# 04_-_CPU_-_DDR3_DDR3_MEM.net
KiCad netlist of a schematic drawn in Altium Designer
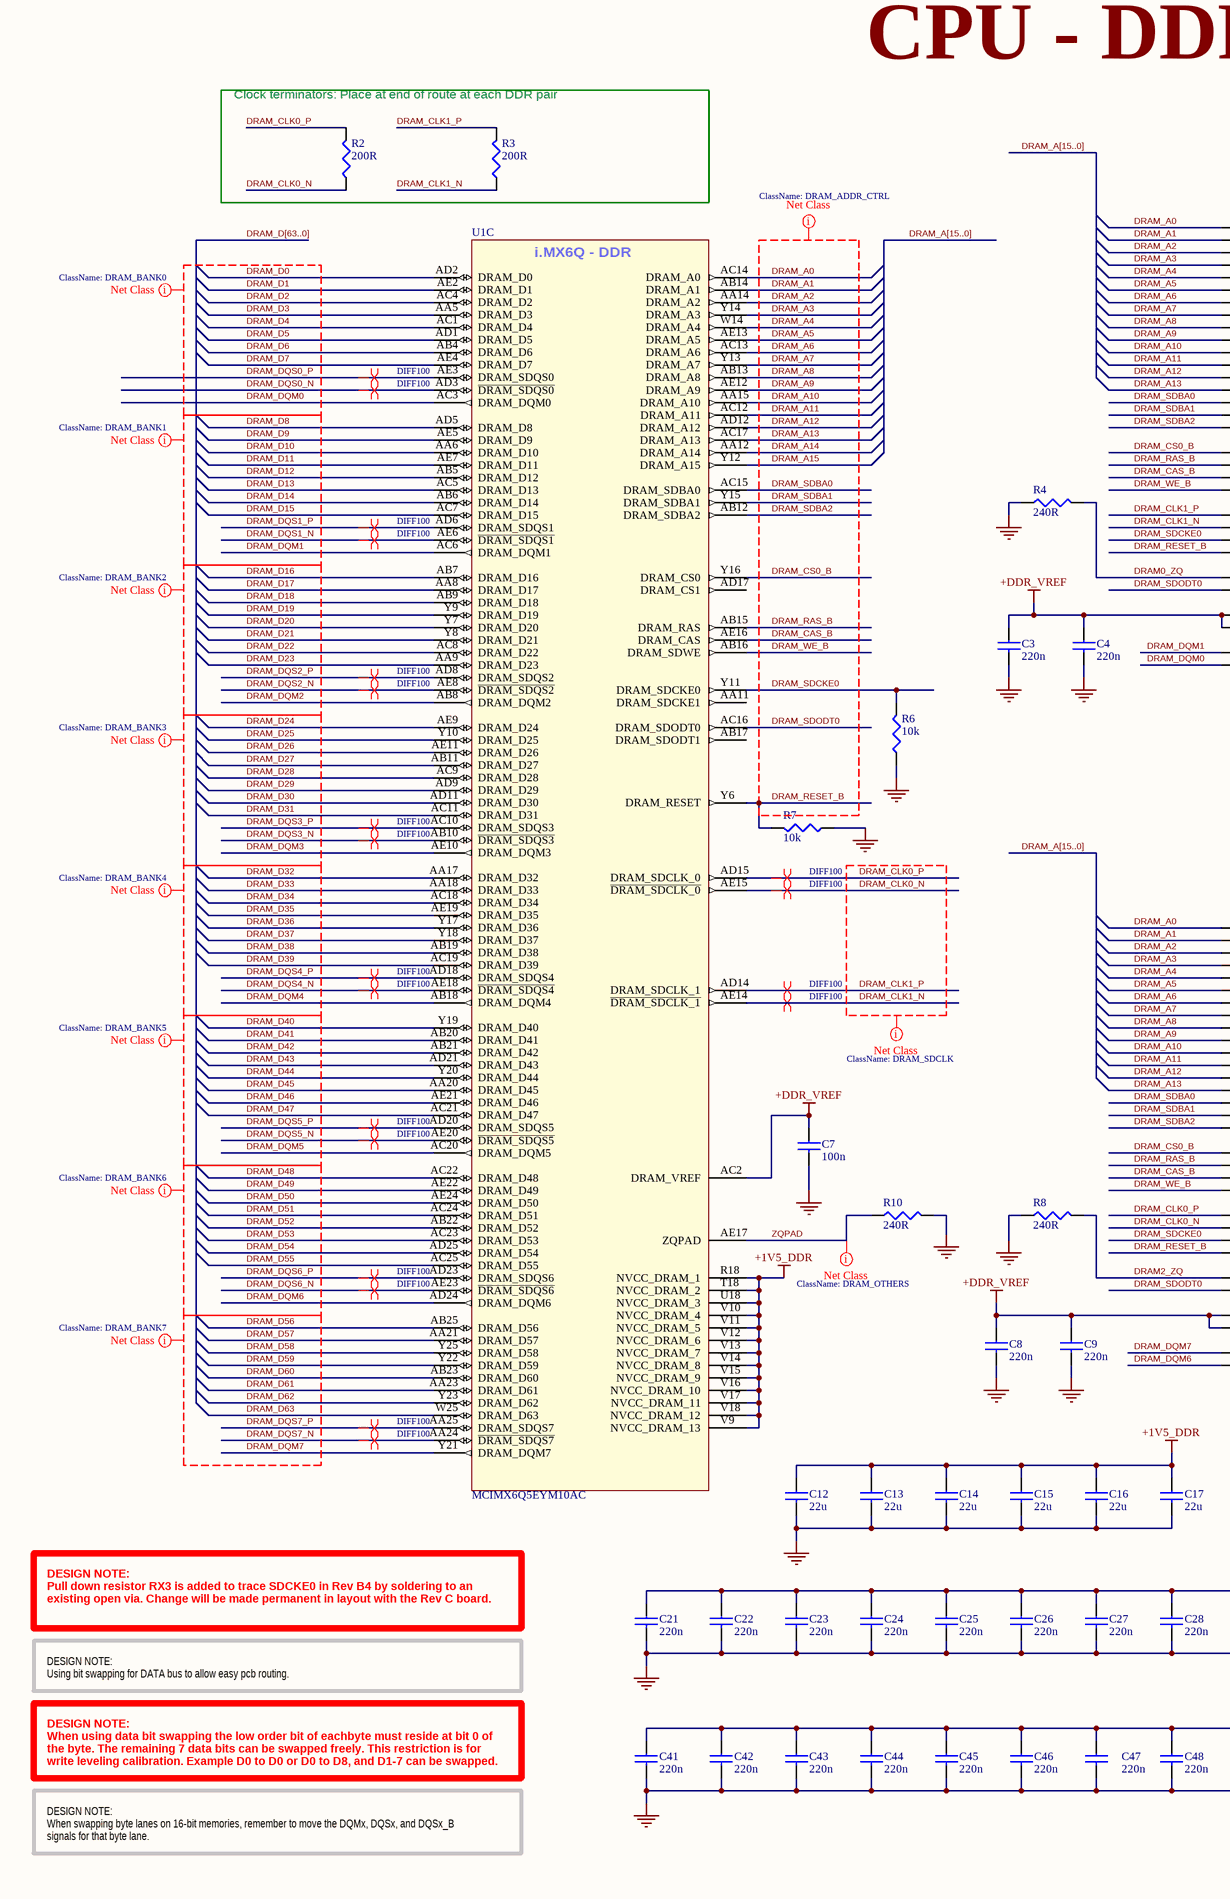
[diagram p0: [04] - CPU - DDR3, DDR3 MEM.SchDoc, left]
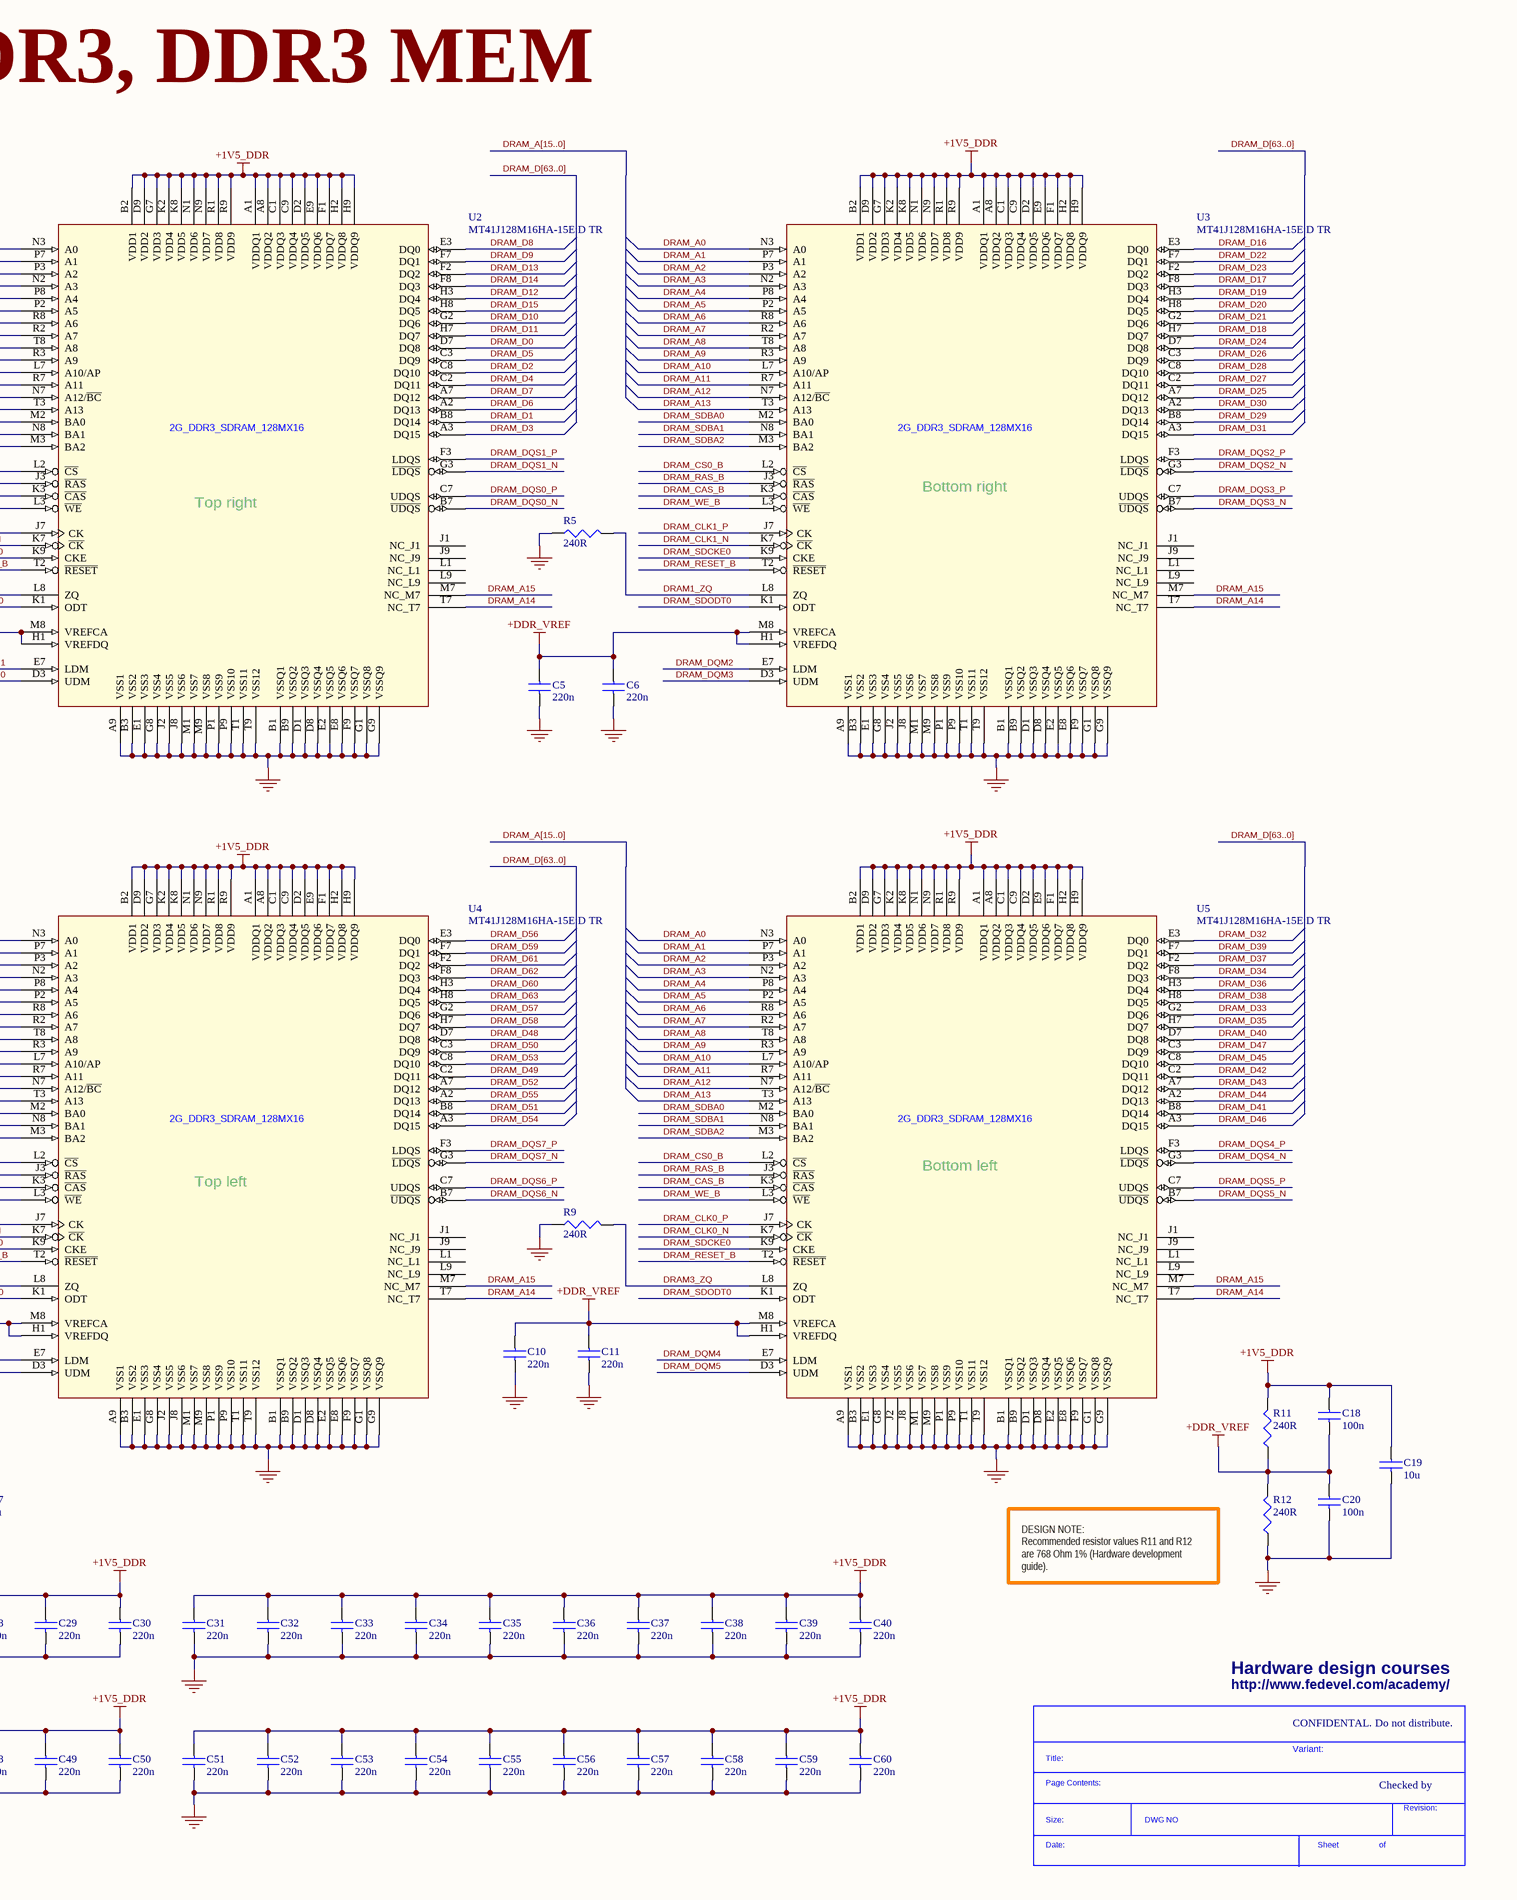
[diagram p1: [04] - CPU - DDR3, DDR3 MEM.SchDoc, right]

(export (version "E")
  (design (tool "Eeschema 10.0.6"))
  (components
    (comp (ref "C3")
      (value "220n")
      (footprint "C0402")
      (description "CAP CER .22UF 25V X5R 20% 0402")
      (fields
        (field (name "MANUFACTURER") "TDK Corporation")
        (field (name "MANUFACTURER PART NUMBER") "C1005X5R1E224M")
      )
      (libsource (lib "iMX6 Rex_V1I1") (part "C1005X5R1E224M"))
    )
    (comp (ref "C4")
      (value "220n")
      (footprint "C0402")
      (description "CAP CER .22UF 25V X5R 20% 0402")
      (fields
        (field (name "MANUFACTURER") "TDK Corporation")
        (field (name "MANUFACTURER PART NUMBER") "C1005X5R1E224M")
      )
      (libsource (lib "iMX6 Rex_V1I1") (part "C1005X5R1E224M"))
    )
    (comp (ref "C5")
      (value "220n")
      (footprint "C0402")
      (description "CAP CER .22UF 25V X5R 20% 0402")
      (fields
        (field (name "MANUFACTURER") "TDK Corporation")
        (field (name "MANUFACTURER PART NUMBER") "C1005X5R1E224M")
      )
      (libsource (lib "iMX6 Rex_V1I1") (part "C1005X5R1E224M"))
    )
    (comp (ref "C6")
      (value "220n")
      (footprint "C0402")
      (description "CAP CER .22UF 25V X5R 20% 0402")
      (fields
        (field (name "MANUFACTURER") "TDK Corporation")
        (field (name "MANUFACTURER PART NUMBER") "C1005X5R1E224M")
      )
      (libsource (lib "iMX6 Rex_V1I1") (part "C1005X5R1E224M"))
    )
    (comp (ref "C7")
      (value "100n")
      (footprint "C0402")
      (description "CAP CER .10UF 50V X5R 10% 0402")
      (fields
        (field (name "MANUFACTURER") "TDK Corporation")
        (field (name "MANUFACTURER PART NUMBER") "C1005X5R1H104K")
      )
      (libsource (lib "iMX6 Rex_V1I1") (part "C1005X5R1H104K"))
    )
    (comp (ref "C8")
      (value "220n")
      (footprint "C0402")
      (description "CAP CER .22UF 25V X5R 20% 0402")
      (fields
        (field (name "MANUFACTURER") "TDK Corporation")
        (field (name "MANUFACTURER PART NUMBER") "C1005X5R1E224M")
      )
      (libsource (lib "iMX6 Rex_V1I1") (part "C1005X5R1E224M"))
    )
    (comp (ref "C9")
      (value "220n")
      (footprint "C0402")
      (description "CAP CER .22UF 25V X5R 20% 0402")
      (fields
        (field (name "MANUFACTURER") "TDK Corporation")
        (field (name "MANUFACTURER PART NUMBER") "C1005X5R1E224M")
      )
      (libsource (lib "iMX6 Rex_V1I1") (part "C1005X5R1E224M"))
    )
    (comp (ref "C10")
      (value "220n")
      (footprint "C0402")
      (description "CAP CER .22UF 25V X5R 20% 0402")
      (fields
        (field (name "MANUFACTURER") "TDK Corporation")
        (field (name "MANUFACTURER PART NUMBER") "C1005X5R1E224M")
      )
      (libsource (lib "iMX6 Rex_V1I1") (part "C1005X5R1E224M"))
    )
    (comp (ref "C11")
      (value "220n")
      (footprint "C0402")
      (description "CAP CER .22UF 25V X5R 20% 0402")
      (fields
        (field (name "MANUFACTURER") "TDK Corporation")
        (field (name "MANUFACTURER PART NUMBER") "C1005X5R1E224M")
      )
      (libsource (lib "iMX6 Rex_V1I1") (part "C1005X5R1E224M"))
    )
    (comp (ref "C12")
      (value "22u")
      (footprint "C0603")
      (description "CAP CER 22UF 4V 20% X5R 0603")
      (fields
        (field (name "MANUFACTURER") "Murata Electronics North America")
        (field (name "MANUFACTURER PART NUMBER") "GRM188R60G226MEA0L")
        (field (name ".CHECKED PCB") "RF, used by MM")
        (field (name ".CHECKED SCH") "MM, checked by RF")
        (field (name ".CREATOR") "MM")
      )
      (libsource (lib "iMX6 Rex_V1I1") (part "GRM188R60G226MEA0L"))
    )
    (comp (ref "C13")
      (value "22u")
      (footprint "C0603")
      (description "CAP CER 22UF 4V 20% X5R 0603")
      (fields
        (field (name "MANUFACTURER") "Murata Electronics North America")
        (field (name "MANUFACTURER PART NUMBER") "GRM188R60G226MEA0L")
        (field (name ".CHECKED PCB") "RF, used by MM")
        (field (name ".CHECKED SCH") "MM, checked by RF")
        (field (name ".CREATOR") "MM")
      )
      (libsource (lib "iMX6 Rex_V1I1") (part "GRM188R60G226MEA0L"))
    )
    (comp (ref "C14")
      (value "22u")
      (footprint "C0603")
      (description "CAP CER 22UF 4V 20% X5R 0603")
      (fields
        (field (name "MANUFACTURER") "Murata Electronics North America")
        (field (name "MANUFACTURER PART NUMBER") "GRM188R60G226MEA0L")
        (field (name ".CHECKED PCB") "RF, used by MM")
        (field (name ".CHECKED SCH") "MM, checked by RF")
        (field (name ".CREATOR") "MM")
      )
      (libsource (lib "iMX6 Rex_V1I1") (part "GRM188R60G226MEA0L"))
    )
    (comp (ref "C15")
      (value "22u")
      (footprint "C0603")
      (description "CAP CER 22UF 4V 20% X5R 0603")
      (fields
        (field (name "MANUFACTURER") "Murata Electronics North America")
        (field (name "MANUFACTURER PART NUMBER") "GRM188R60G226MEA0L")
        (field (name ".CHECKED PCB") "RF, used by MM")
        (field (name ".CHECKED SCH") "MM, checked by RF")
        (field (name ".CREATOR") "MM")
      )
      (libsource (lib "iMX6 Rex_V1I1") (part "GRM188R60G226MEA0L"))
    )
    (comp (ref "C16")
      (value "22u")
      (footprint "C0603")
      (description "CAP CER 22UF 4V 20% X5R 0603")
      (fields
        (field (name "MANUFACTURER") "Murata Electronics North America")
        (field (name "MANUFACTURER PART NUMBER") "GRM188R60G226MEA0L")
        (field (name ".CHECKED PCB") "RF, used by MM")
        (field (name ".CHECKED SCH") "MM, checked by RF")
        (field (name ".CREATOR") "MM")
      )
      (libsource (lib "iMX6 Rex_V1I1") (part "GRM188R60G226MEA0L"))
    )
    (comp (ref "C17")
      (value "22u")
      (footprint "C0603")
      (description "CAP CER 22UF 4V 20% X5R 0603")
      (fields
        (field (name "MANUFACTURER") "Murata Electronics North America")
        (field (name "MANUFACTURER PART NUMBER") "GRM188R60G226MEA0L")
        (field (name ".CHECKED PCB") "RF, used by MM")
        (field (name ".CHECKED SCH") "MM, checked by RF")
        (field (name ".CREATOR") "MM")
      )
      (libsource (lib "iMX6 Rex_V1I1") (part "GRM188R60G226MEA0L"))
    )
    (comp (ref "C18")
      (value "100n")
      (footprint "C0402")
      (description "CAP CER .10UF 50V X5R 10% 0402")
      (fields
        (field (name "MANUFACTURER") "TDK Corporation")
        (field (name "MANUFACTURER PART NUMBER") "C1005X5R1H104K")
      )
      (libsource (lib "iMX6 Rex_V1I1") (part "C1005X5R1H104K"))
    )
    (comp (ref "C19")
      (value "10u")
      (footprint "C0603")
      (description "CAP CER 10UF 6.3V X5R 20% 0603")
      (fields
        (field (name "MANUFACTURER") "TDK Corporation")
        (field (name "MANUFACTURER PART NUMBER") "C1608X5R0J106M")
      )
      (libsource (lib "iMX6 Rex_V1I1") (part "C1608X5R0J106M"))
    )
    (comp (ref "C20")
      (value "100n")
      (footprint "C0402")
      (description "CAP CER .10UF 50V X5R 10% 0402")
      (fields
        (field (name "MANUFACTURER") "TDK Corporation")
        (field (name "MANUFACTURER PART NUMBER") "C1005X5R1H104K")
      )
      (libsource (lib "iMX6 Rex_V1I1") (part "C1005X5R1H104K"))
    )
    (comp (ref "C21")
      (value "220n")
      (footprint "C0402")
      (description "CAP CER .22UF 25V X5R 20% 0402")
      (fields
        (field (name "MANUFACTURER") "TDK Corporation")
        (field (name "MANUFACTURER PART NUMBER") "C1005X5R1E224M")
      )
      (libsource (lib "iMX6 Rex_V1I1") (part "C1005X5R1E224M"))
    )
    (comp (ref "C22")
      (value "220n")
      (footprint "C0402")
      (description "CAP CER .22UF 25V X5R 20% 0402")
      (fields
        (field (name "MANUFACTURER") "TDK Corporation")
        (field (name "MANUFACTURER PART NUMBER") "C1005X5R1E224M")
      )
      (libsource (lib "iMX6 Rex_V1I1") (part "C1005X5R1E224M"))
    )
    (comp (ref "C23")
      (value "220n")
      (footprint "C0402")
      (description "CAP CER .22UF 25V X5R 20% 0402")
      (fields
        (field (name "MANUFACTURER") "TDK Corporation")
        (field (name "MANUFACTURER PART NUMBER") "C1005X5R1E224M")
      )
      (libsource (lib "iMX6 Rex_V1I1") (part "C1005X5R1E224M"))
    )
    (comp (ref "C24")
      (value "220n")
      (footprint "C0402")
      (description "CAP CER .22UF 25V X5R 20% 0402")
      (fields
        (field (name "MANUFACTURER") "TDK Corporation")
        (field (name "MANUFACTURER PART NUMBER") "C1005X5R1E224M")
      )
      (libsource (lib "iMX6 Rex_V1I1") (part "C1005X5R1E224M"))
    )
    (comp (ref "C25")
      (value "220n")
      (footprint "C0402")
      (description "CAP CER .22UF 25V X5R 20% 0402")
      (fields
        (field (name "MANUFACTURER") "TDK Corporation")
        (field (name "MANUFACTURER PART NUMBER") "C1005X5R1E224M")
      )
      (libsource (lib "iMX6 Rex_V1I1") (part "C1005X5R1E224M"))
    )
    (comp (ref "C26")
      (value "220n")
      (footprint "C0402")
      (description "CAP CER .22UF 25V X5R 20% 0402")
      (fields
        (field (name "MANUFACTURER") "TDK Corporation")
        (field (name "MANUFACTURER PART NUMBER") "C1005X5R1E224M")
      )
      (libsource (lib "iMX6 Rex_V1I1") (part "C1005X5R1E224M"))
    )
    (comp (ref "C27")
      (value "220n")
      (footprint "C0402")
      (description "CAP CER .22UF 25V X5R 20% 0402")
      (fields
        (field (name "MANUFACTURER") "TDK Corporation")
        (field (name "MANUFACTURER PART NUMBER") "C1005X5R1E224M")
      )
      (libsource (lib "iMX6 Rex_V1I1") (part "C1005X5R1E224M"))
    )
    (comp (ref "C28")
      (value "220n")
      (footprint "C0402")
      (description "CAP CER .22UF 25V X5R 20% 0402")
      (fields
        (field (name "MANUFACTURER") "TDK Corporation")
        (field (name "MANUFACTURER PART NUMBER") "C1005X5R1E224M")
      )
      (libsource (lib "iMX6 Rex_V1I1") (part "C1005X5R1E224M"))
    )
    (comp (ref "C29")
      (value "220n")
      (footprint "C0402")
      (description "CAP CER .22UF 25V X5R 20% 0402")
      (fields
        (field (name "MANUFACTURER") "TDK Corporation")
        (field (name "MANUFACTURER PART NUMBER") "C1005X5R1E224M")
      )
      (libsource (lib "iMX6 Rex_V1I1") (part "C1005X5R1E224M"))
    )
    (comp (ref "C30")
      (value "220n")
      (footprint "C0402")
      (description "CAP CER .22UF 25V X5R 20% 0402")
      (fields
        (field (name "MANUFACTURER") "TDK Corporation")
        (field (name "MANUFACTURER PART NUMBER") "C1005X5R1E224M")
      )
      (libsource (lib "iMX6 Rex_V1I1") (part "C1005X5R1E224M"))
    )
    (comp (ref "C31")
      (value "220n")
      (footprint "C0402")
      (description "CAP CER .22UF 25V X5R 20% 0402")
      (fields
        (field (name "MANUFACTURER") "TDK Corporation")
        (field (name "MANUFACTURER PART NUMBER") "C1005X5R1E224M")
      )
      (libsource (lib "iMX6 Rex_V1I1") (part "C1005X5R1E224M"))
    )
    (comp (ref "C32")
      (value "220n")
      (footprint "C0402")
      (description "CAP CER .22UF 25V X5R 20% 0402")
      (fields
        (field (name "MANUFACTURER") "TDK Corporation")
        (field (name "MANUFACTURER PART NUMBER") "C1005X5R1E224M")
      )
      (libsource (lib "iMX6 Rex_V1I1") (part "C1005X5R1E224M"))
    )
    (comp (ref "C33")
      (value "220n")
      (footprint "C0402")
      (description "CAP CER .22UF 25V X5R 20% 0402")
      (fields
        (field (name "MANUFACTURER") "TDK Corporation")
        (field (name "MANUFACTURER PART NUMBER") "C1005X5R1E224M")
      )
      (libsource (lib "iMX6 Rex_V1I1") (part "C1005X5R1E224M"))
    )
    (comp (ref "C34")
      (value "220n")
      (footprint "C0402")
      (description "CAP CER .22UF 25V X5R 20% 0402")
      (fields
        (field (name "MANUFACTURER") "TDK Corporation")
        (field (name "MANUFACTURER PART NUMBER") "C1005X5R1E224M")
      )
      (libsource (lib "iMX6 Rex_V1I1") (part "C1005X5R1E224M"))
    )
    (comp (ref "C35")
      (value "220n")
      (footprint "C0402")
      (description "CAP CER .22UF 25V X5R 20% 0402")
      (fields
        (field (name "MANUFACTURER") "TDK Corporation")
        (field (name "MANUFACTURER PART NUMBER") "C1005X5R1E224M")
      )
      (libsource (lib "iMX6 Rex_V1I1") (part "C1005X5R1E224M"))
    )
    (comp (ref "C36")
      (value "220n")
      (footprint "C0402")
      (description "CAP CER .22UF 25V X5R 20% 0402")
      (fields
        (field (name "MANUFACTURER") "TDK Corporation")
        (field (name "MANUFACTURER PART NUMBER") "C1005X5R1E224M")
      )
      (libsource (lib "iMX6 Rex_V1I1") (part "C1005X5R1E224M"))
    )
    (comp (ref "C37")
      (value "220n")
      (footprint "C0402")
      (description "CAP CER .22UF 25V X5R 20% 0402")
      (fields
        (field (name "MANUFACTURER") "TDK Corporation")
        (field (name "MANUFACTURER PART NUMBER") "C1005X5R1E224M")
      )
      (libsource (lib "iMX6 Rex_V1I1") (part "C1005X5R1E224M"))
    )
    (comp (ref "C38")
      (value "220n")
      (footprint "C0402")
      (description "CAP CER .22UF 25V X5R 20% 0402")
      (fields
        (field (name "MANUFACTURER") "TDK Corporation")
        (field (name "MANUFACTURER PART NUMBER") "C1005X5R1E224M")
      )
      (libsource (lib "iMX6 Rex_V1I1") (part "C1005X5R1E224M"))
    )
    (comp (ref "C39")
      (value "220n")
      (footprint "C0402")
      (description "CAP CER .22UF 25V X5R 20% 0402")
      (fields
        (field (name "MANUFACTURER") "TDK Corporation")
        (field (name "MANUFACTURER PART NUMBER") "C1005X5R1E224M")
      )
      (libsource (lib "iMX6 Rex_V1I1") (part "C1005X5R1E224M"))
    )
    (comp (ref "C40")
      (value "220n")
      (footprint "C0402")
      (description "CAP CER .22UF 25V X5R 20% 0402")
      (fields
        (field (name "MANUFACTURER") "TDK Corporation")
        (field (name "MANUFACTURER PART NUMBER") "C1005X5R1E224M")
      )
      (libsource (lib "iMX6 Rex_V1I1") (part "C1005X5R1E224M"))
    )
    (comp (ref "C41")
      (value "220n")
      (footprint "C0402")
      (description "CAP CER .22UF 25V X5R 20% 0402")
      (fields
        (field (name "MANUFACTURER") "TDK Corporation")
        (field (name "MANUFACTURER PART NUMBER") "C1005X5R1E224M")
      )
      (libsource (lib "iMX6 Rex_V1I1") (part "C1005X5R1E224M"))
    )
    (comp (ref "C42")
      (value "220n")
      (footprint "C0402")
      (description "CAP CER .22UF 25V X5R 20% 0402")
      (fields
        (field (name "MANUFACTURER") "TDK Corporation")
        (field (name "MANUFACTURER PART NUMBER") "C1005X5R1E224M")
      )
      (libsource (lib "iMX6 Rex_V1I1") (part "C1005X5R1E224M"))
    )
    (comp (ref "C43")
      (value "220n")
      (footprint "C0402")
      (description "CAP CER .22UF 25V X5R 20% 0402")
      (fields
        (field (name "MANUFACTURER") "TDK Corporation")
        (field (name "MANUFACTURER PART NUMBER") "C1005X5R1E224M")
      )
      (libsource (lib "iMX6 Rex_V1I1") (part "C1005X5R1E224M"))
    )
    (comp (ref "C44")
      (value "220n")
      (footprint "C0402")
      (description "CAP CER .22UF 25V X5R 20% 0402")
      (fields
        (field (name "MANUFACTURER") "TDK Corporation")
        (field (name "MANUFACTURER PART NUMBER") "C1005X5R1E224M")
      )
      (libsource (lib "iMX6 Rex_V1I1") (part "C1005X5R1E224M"))
    )
    (comp (ref "C45")
      (value "220n")
      (footprint "C0402")
      (description "CAP CER .22UF 25V X5R 20% 0402")
      (fields
        (field (name "MANUFACTURER") "TDK Corporation")
        (field (name "MANUFACTURER PART NUMBER") "C1005X5R1E224M")
      )
      (libsource (lib "iMX6 Rex_V1I1") (part "C1005X5R1E224M"))
    )
    (comp (ref "C46")
      (value "220n")
      (footprint "C0402")
      (description "CAP CER .22UF 25V X5R 20% 0402")
      (fields
        (field (name "MANUFACTURER") "TDK Corporation")
        (field (name "MANUFACTURER PART NUMBER") "C1005X5R1E224M")
      )
      (libsource (lib "iMX6 Rex_V1I1") (part "C1005X5R1E224M"))
    )
    (comp (ref "C47")
      (value "220n")
      (footprint "C0402")
      (description "CAP CER .22UF 25V X5R 20% 0402")
      (fields
        (field (name "MANUFACTURER") "TDK Corporation")
        (field (name "MANUFACTURER PART NUMBER") "C1005X5R1E224M")
      )
      (libsource (lib "iMX6 Rex_V1I1") (part "C1005X5R1E224M"))
    )
    (comp (ref "C48")
      (value "220n")
      (footprint "C0402")
      (description "CAP CER .22UF 25V X5R 20% 0402")
      (fields
        (field (name "MANUFACTURER") "TDK Corporation")
        (field (name "MANUFACTURER PART NUMBER") "C1005X5R1E224M")
      )
      (libsource (lib "iMX6 Rex_V1I1") (part "C1005X5R1E224M"))
    )
    (comp (ref "C49")
      (value "220n")
      (footprint "C0402")
      (description "CAP CER .22UF 25V X5R 20% 0402")
      (fields
        (field (name "MANUFACTURER") "TDK Corporation")
        (field (name "MANUFACTURER PART NUMBER") "C1005X5R1E224M")
      )
      (libsource (lib "iMX6 Rex_V1I1") (part "C1005X5R1E224M"))
    )
    (comp (ref "C50")
      (value "220n")
      (footprint "C0402")
      (description "CAP CER .22UF 25V X5R 20% 0402")
      (fields
        (field (name "MANUFACTURER") "TDK Corporation")
        (field (name "MANUFACTURER PART NUMBER") "C1005X5R1E224M")
      )
      (libsource (lib "iMX6 Rex_V1I1") (part "C1005X5R1E224M"))
    )
    (comp (ref "C51")
      (value "220n")
      (footprint "C0402")
      (description "CAP CER .22UF 25V X5R 20% 0402")
      (fields
        (field (name "MANUFACTURER") "TDK Corporation")
        (field (name "MANUFACTURER PART NUMBER") "C1005X5R1E224M")
      )
      (libsource (lib "iMX6 Rex_V1I1") (part "C1005X5R1E224M"))
    )
    (comp (ref "C52")
      (value "220n")
      (footprint "C0402")
      (description "CAP CER .22UF 25V X5R 20% 0402")
      (fields
        (field (name "MANUFACTURER") "TDK Corporation")
        (field (name "MANUFACTURER PART NUMBER") "C1005X5R1E224M")
      )
      (libsource (lib "iMX6 Rex_V1I1") (part "C1005X5R1E224M"))
    )
    (comp (ref "C53")
      (value "220n")
      (footprint "C0402")
      (description "CAP CER .22UF 25V X5R 20% 0402")
      (fields
        (field (name "MANUFACTURER") "TDK Corporation")
        (field (name "MANUFACTURER PART NUMBER") "C1005X5R1E224M")
      )
      (libsource (lib "iMX6 Rex_V1I1") (part "C1005X5R1E224M"))
    )
    (comp (ref "C54")
      (value "220n")
      (footprint "C0402")
      (description "CAP CER .22UF 25V X5R 20% 0402")
      (fields
        (field (name "MANUFACTURER") "TDK Corporation")
        (field (name "MANUFACTURER PART NUMBER") "C1005X5R1E224M")
      )
      (libsource (lib "iMX6 Rex_V1I1") (part "C1005X5R1E224M"))
    )
    (comp (ref "C55")
      (value "220n")
      (footprint "C0402")
      (description "CAP CER .22UF 25V X5R 20% 0402")
      (fields
        (field (name "MANUFACTURER") "TDK Corporation")
        (field (name "MANUFACTURER PART NUMBER") "C1005X5R1E224M")
      )
      (libsource (lib "iMX6 Rex_V1I1") (part "C1005X5R1E224M"))
    )
    (comp (ref "C56")
      (value "220n")
      (footprint "C0402")
      (description "CAP CER .22UF 25V X5R 20% 0402")
      (fields
        (field (name "MANUFACTURER") "TDK Corporation")
        (field (name "MANUFACTURER PART NUMBER") "C1005X5R1E224M")
      )
      (libsource (lib "iMX6 Rex_V1I1") (part "C1005X5R1E224M"))
    )
    (comp (ref "C57")
      (value "220n")
      (footprint "C0402")
      (description "CAP CER .22UF 25V X5R 20% 0402")
      (fields
        (field (name "MANUFACTURER") "TDK Corporation")
        (field (name "MANUFACTURER PART NUMBER") "C1005X5R1E224M")
      )
      (libsource (lib "iMX6 Rex_V1I1") (part "C1005X5R1E224M"))
    )
    (comp (ref "C58")
      (value "220n")
      (footprint "C0402")
      (description "CAP CER .22UF 25V X5R 20% 0402")
      (fields
        (field (name "MANUFACTURER") "TDK Corporation")
        (field (name "MANUFACTURER PART NUMBER") "C1005X5R1E224M")
      )
      (libsource (lib "iMX6 Rex_V1I1") (part "C1005X5R1E224M"))
    )
    (comp (ref "C59")
      (value "220n")
      (footprint "C0402")
      (description "CAP CER .22UF 25V X5R 20% 0402")
      (fields
        (field (name "MANUFACTURER") "TDK Corporation")
        (field (name "MANUFACTURER PART NUMBER") "C1005X5R1E224M")
      )
      (libsource (lib "iMX6 Rex_V1I1") (part "C1005X5R1E224M"))
    )
    (comp (ref "C60")
      (value "220n")
      (footprint "C0402")
      (description "CAP CER .22UF 25V X5R 20% 0402")
      (fields
        (field (name "MANUFACTURER") "TDK Corporation")
        (field (name "MANUFACTURER PART NUMBER") "C1005X5R1E224M")
      )
      (libsource (lib "iMX6 Rex_V1I1") (part "C1005X5R1E224M"))
    )
    (comp (ref "R2")
      (value "200R")
      (footprint "R0402")
      (description "RES 200 OHM 1/16W 1% 0402 SMD")
      (fields
        (field (name "MANUFACTURER") "Vishay Dale")
        (field (name "MANUFACTURER PART NUMBER") "CRCW0402200RFKED")
        (field (name ".CHECKED PCB") "RF, used by MM")
        (field (name ".CHECKED SCH") "MM, checked by RF")
        (field (name ".CREATOR") "MM")
      )
      (libsource (lib "iMX6 Rex_V1I1") (part "CRCW0402200RFKED"))
    )
    (comp (ref "R3")
      (value "200R")
      (footprint "R0402")
      (description "RES 200 OHM 1/16W 1% 0402 SMD")
      (fields
        (field (name "MANUFACTURER") "Vishay Dale")
        (field (name "MANUFACTURER PART NUMBER") "CRCW0402200RFKED")
        (field (name ".CHECKED PCB") "RF, used by MM")
        (field (name ".CHECKED SCH") "MM, checked by RF")
        (field (name ".CREATOR") "MM")
      )
      (libsource (lib "iMX6 Rex_V1I1") (part "CRCW0402200RFKED"))
    )
    (comp (ref "R4")
      (value "240R")
      (footprint "R0402")
      (description "RES TF 240 OHM 1% 0.0625W 0402")
      (fields
        (field (name "MANUFACTURER") "Stackpole Electronics Inc")
        (field (name "MANUFACTURER PART NUMBER") "RMCF0402FT240R")
      )
      (libsource (lib "iMX6 Rex_V1I1") (part "RMCF0402FT240R"))
    )
    (comp (ref "R5")
      (value "240R")
      (footprint "R0402")
      (description "RES TF 240 OHM 1% 0.0625W 0402")
      (fields
        (field (name "MANUFACTURER") "Stackpole Electronics Inc")
        (field (name "MANUFACTURER PART NUMBER") "RMCF0402FT240R")
      )
      (libsource (lib "iMX6 Rex_V1I1") (part "RMCF0402FT240R"))
    )
    (comp (ref "R6")
      (value "10k")
      (footprint "R0402")
      (description "RES 10.0K OHM 1/16W 1% 0402 SMD")
      (fields
        (field (name "MANUFACTURER") "Yageo")
        (field (name "MANUFACTURER PART NUMBER") "RC0402FR-0710KL")
      )
      (libsource (lib "iMX6 Rex_V1I1") (part "RC0402FR-0710KL"))
    )
    (comp (ref "R7")
      (value "10k")
      (footprint "R0402")
      (description "RES 10.0K OHM 1/16W 1% 0402 SMD")
      (fields
        (field (name "MANUFACTURER") "Yageo")
        (field (name "MANUFACTURER PART NUMBER") "RC0402FR-0710KL")
      )
      (libsource (lib "iMX6 Rex_V1I1") (part "RC0402FR-0710KL"))
    )
    (comp (ref "R8")
      (value "240R")
      (footprint "R0402")
      (description "RES TF 240 OHM 1% 0.0625W 0402")
      (fields
        (field (name "MANUFACTURER") "Stackpole Electronics Inc")
        (field (name "MANUFACTURER PART NUMBER") "RMCF0402FT240R")
      )
      (libsource (lib "iMX6 Rex_V1I1") (part "RMCF0402FT240R"))
    )
    (comp (ref "R9")
      (value "240R")
      (footprint "R0402")
      (description "RES TF 240 OHM 1% 0.0625W 0402")
      (fields
        (field (name "MANUFACTURER") "Stackpole Electronics Inc")
        (field (name "MANUFACTURER PART NUMBER") "RMCF0402FT240R")
      )
      (libsource (lib "iMX6 Rex_V1I1") (part "RMCF0402FT240R"))
    )
    (comp (ref "R10")
      (value "240R")
      (footprint "R0402")
      (description "RES TF 240 OHM 1% 0.0625W 0402")
      (fields
        (field (name "MANUFACTURER") "Stackpole Electronics Inc")
        (field (name "MANUFACTURER PART NUMBER") "RMCF0402FT240R")
      )
      (libsource (lib "iMX6 Rex_V1I1") (part "RMCF0402FT240R"))
    )
    (comp (ref "R11")
      (value "240R")
      (footprint "R0402")
      (description "RES TF 240 OHM 1% 0.0625W 0402")
      (fields
        (field (name "MANUFACTURER") "Stackpole Electronics Inc")
        (field (name "MANUFACTURER PART NUMBER") "RMCF0402FT240R")
      )
      (libsource (lib "iMX6 Rex_V1I1") (part "RMCF0402FT240R"))
    )
    (comp (ref "R12")
      (value "240R")
      (footprint "R0402")
      (description "RES TF 240 OHM 1% 0.0625W 0402")
      (fields
        (field (name "MANUFACTURER") "Stackpole Electronics Inc")
        (field (name "MANUFACTURER PART NUMBER") "RMCF0402FT240R")
      )
      (libsource (lib "iMX6 Rex_V1I1") (part "RMCF0402FT240R"))
    )
    (comp (ref "U1")
      (value "MCIMX6Q5EYM10AC")
      (footprint "PBGA624")
      (description "IC MCU 32BIT ARM QUAD 624FCBGA")
      (fields
        (field (name "MANUFACTURER") "Freescale Semiconductor")
        (field (name ".CREATOR") "MM")
        (field (name ".CHECKED PCB") "MM, checked by RF")
        (field (name ".CHECKED SCH") "MM")
      )
      (libsource (lib "iMX6 Rex_V1I1") (part "MCIMX6Q5EYM10AC"))
    )
    (comp (ref "U2")
      (value "MT41J128M16HA-15E:D TR")
      (footprint "96_FPGA_DD3")
      (description "IC DDR3 SDRAM 2GBIT 667MHZ 96BGA")
      (fields
        (field (name "MANUFACTURER") "Micron Technology Inc")
        (field (name ".CREATOR") "MM")
        (field (name ".CHECKED PCB") "RF, used by MM")
        (field (name ".CHECKED SCH") "MM, checked by RF")
      )
      (libsource (lib "iMX6 Rex_V1I1") (part "MT41J128M16HA-15E{colon}D TR"))
    )
    (comp (ref "U3")
      (value "MT41J128M16HA-15E:D TR")
      (footprint "96_FPGA_DD3")
      (description "IC DDR3 SDRAM 2GBIT 667MHZ 96BGA")
      (fields
        (field (name "MANUFACTURER") "Micron Technology Inc")
        (field (name ".CREATOR") "MM")
        (field (name ".CHECKED PCB") "RF, used by MM")
        (field (name ".CHECKED SCH") "MM, checked by RF")
      )
      (libsource (lib "iMX6 Rex_V1I1") (part "MT41J128M16HA-15E{colon}D TR"))
    )
    (comp (ref "U4")
      (value "MT41J128M16HA-15E:D TR")
      (footprint "96_FPGA_DD3")
      (description "IC DDR3 SDRAM 2GBIT 667MHZ 96BGA")
      (fields
        (field (name "MANUFACTURER") "Micron Technology Inc")
        (field (name ".CREATOR") "MM")
        (field (name ".CHECKED PCB") "RF, used by MM")
        (field (name ".CHECKED SCH") "MM, checked by RF")
      )
      (libsource (lib "iMX6 Rex_V1I1") (part "MT41J128M16HA-15E{colon}D TR"))
    )
    (comp (ref "U5")
      (value "MT41J128M16HA-15E:D TR")
      (footprint "96_FPGA_DD3")
      (description "IC DDR3 SDRAM 2GBIT 667MHZ 96BGA")
      (fields
        (field (name "MANUFACTURER") "Micron Technology Inc")
        (field (name ".CREATOR") "MM")
        (field (name ".CHECKED PCB") "RF, used by MM")
        (field (name ".CHECKED SCH") "MM, checked by RF")
      )
      (libsource (lib "iMX6 Rex_V1I1") (part "MT41J128M16HA-15E{colon}D TR"))
    )
  )
  (nets
    (net (code "1") (name "+1V5_DDR") (class "Default")
      (node (ref "C12") (pin "1") (pinfunction "1_1") (pintype "passive"))
      (node (ref "C13") (pin "1") (pinfunction "1_1") (pintype "passive"))
      (node (ref "C14") (pin "1") (pinfunction "1_1") (pintype "passive"))
      (node (ref "C15") (pin "1") (pinfunction "1_1") (pintype "passive"))
      (node (ref "C16") (pin "1") (pinfunction "1_1") (pintype "passive"))
      (node (ref "C17") (pin "1") (pinfunction "1_1") (pintype "passive"))
      (node (ref "C18") (pin "1") (pinfunction "1_1") (pintype "passive"))
      (node (ref "C19") (pin "1") (pinfunction "1_1") (pintype "passive"))
      (node (ref "C21") (pin "1") (pinfunction "1_1") (pintype "passive"))
      (node (ref "C22") (pin "1") (pinfunction "1_1") (pintype "passive"))
      (node (ref "C23") (pin "1") (pinfunction "1_1") (pintype "passive"))
      (node (ref "C24") (pin "1") (pinfunction "1_1") (pintype "passive"))
      (node (ref "C25") (pin "1") (pinfunction "1_1") (pintype "passive"))
      (node (ref "C26") (pin "1") (pinfunction "1_1") (pintype "passive"))
      (node (ref "C27") (pin "1") (pinfunction "1_1") (pintype "passive"))
      (node (ref "C28") (pin "1") (pinfunction "1_1") (pintype "passive"))
      (node (ref "C29") (pin "1") (pinfunction "1_1") (pintype "passive"))
      (node (ref "C30") (pin "1") (pinfunction "1_1") (pintype "passive"))
      (node (ref "C31") (pin "1") (pinfunction "1_1") (pintype "passive"))
      (node (ref "C32") (pin "1") (pinfunction "1_1") (pintype "passive"))
      (node (ref "C33") (pin "1") (pinfunction "1_1") (pintype "passive"))
      (node (ref "C34") (pin "1") (pinfunction "1_1") (pintype "passive"))
      (node (ref "C35") (pin "1") (pinfunction "1_1") (pintype "passive"))
      (node (ref "C36") (pin "1") (pinfunction "1_1") (pintype "passive"))
      (node (ref "C37") (pin "1") (pinfunction "1_1") (pintype "passive"))
      (node (ref "C38") (pin "1") (pinfunction "1_1") (pintype "passive"))
      (node (ref "C39") (pin "1") (pinfunction "1_1") (pintype "passive"))
      (node (ref "C40") (pin "1") (pinfunction "1_1") (pintype "passive"))
      (node (ref "C41") (pin "1") (pinfunction "1_1") (pintype "passive"))
      (node (ref "C42") (pin "1") (pinfunction "1_1") (pintype "passive"))
      (node (ref "C43") (pin "1") (pinfunction "1_1") (pintype "passive"))
      (node (ref "C44") (pin "1") (pinfunction "1_1") (pintype "passive"))
      (node (ref "C45") (pin "1") (pinfunction "1_1") (pintype "passive"))
      (node (ref "C46") (pin "1") (pinfunction "1_1") (pintype "passive"))
      (node (ref "C47") (pin "1") (pinfunction "1_1") (pintype "passive"))
      (node (ref "C48") (pin "1") (pinfunction "1_1") (pintype "passive"))
      (node (ref "C49") (pin "1") (pinfunction "1_1") (pintype "passive"))
      (node (ref "C50") (pin "1") (pinfunction "1_1") (pintype "passive"))
      (node (ref "C51") (pin "1") (pinfunction "1_1") (pintype "passive"))
      (node (ref "C52") (pin "1") (pinfunction "1_1") (pintype "passive"))
      (node (ref "C53") (pin "1") (pinfunction "1_1") (pintype "passive"))
      (node (ref "C54") (pin "1") (pinfunction "1_1") (pintype "passive"))
      (node (ref "C55") (pin "1") (pinfunction "1_1") (pintype "passive"))
      (node (ref "C56") (pin "1") (pinfunction "1_1") (pintype "passive"))
      (node (ref "C57") (pin "1") (pinfunction "1_1") (pintype "passive"))
      (node (ref "C58") (pin "1") (pinfunction "1_1") (pintype "passive"))
      (node (ref "C59") (pin "1") (pinfunction "1_1") (pintype "passive"))
      (node (ref "C60") (pin "1") (pinfunction "1_1") (pintype "passive"))
      (node (ref "R11") (pin "2") (pinfunction "2_2") (pintype "passive"))
      (node (ref "U1") (pin "R18") (pinfunction "NVCC_DRAM_1_R18") (pintype "power_in"))
      (node (ref "U1") (pin "T18") (pinfunction "NVCC_DRAM_2_T18") (pintype "power_in"))
      (node (ref "U1") (pin "U18") (pinfunction "NVCC_DRAM_3_U18") (pintype "power_in"))
      (node (ref "U1") (pin "V10") (pinfunction "NVCC_DRAM_4_V10") (pintype "power_in"))
      (node (ref "U1") (pin "V11") (pinfunction "NVCC_DRAM_5_V11") (pintype "power_in"))
      (node (ref "U1") (pin "V12") (pinfunction "NVCC_DRAM_6_V12") (pintype "power_in"))
      (node (ref "U1") (pin "V13") (pinfunction "NVCC_DRAM_7_V13") (pintype "power_in"))
      (node (ref "U1") (pin "V14") (pinfunction "NVCC_DRAM_8_V14") (pintype "power_in"))
      (node (ref "U1") (pin "V15") (pinfunction "NVCC_DRAM_9_V15") (pintype "power_in"))
      (node (ref "U1") (pin "V16") (pinfunction "NVCC_DRAM_10_V16") (pintype "power_in"))
      (node (ref "U1") (pin "V17") (pinfunction "NVCC_DRAM_11_V17") (pintype "power_in"))
      (node (ref "U1") (pin "V18") (pinfunction "NVCC_DRAM_12_V18") (pintype "power_in"))
      (node (ref "U1") (pin "V9") (pinfunction "NVCC_DRAM_13_V9") (pintype "power_in"))
      (node (ref "U2") (pin "A1") (pinfunction "VDDQ1_A1") (pintype "power_in"))
      (node (ref "U2") (pin "A8") (pinfunction "VDDQ2_A8") (pintype "power_in"))
      (node (ref "U2") (pin "B2") (pinfunction "VDD1_B2") (pintype "power_in"))
      (node (ref "U2") (pin "C1") (pinfunction "VDDQ3_C1") (pintype "power_in"))
      (node (ref "U2") (pin "C9") (pinfunction "VDDQ4_C9") (pintype "power_in"))
      (node (ref "U2") (pin "D2") (pinfunction "VDDQ5_D2") (pintype "power_in"))
      (node (ref "U2") (pin "D9") (pinfunction "VDD2_D9") (pintype "power_in"))
      (node (ref "U2") (pin "E9") (pinfunction "VDDQ6_E9") (pintype "power_in"))
      (node (ref "U2") (pin "F1") (pinfunction "VDDQ7_F1") (pintype "power_in"))
      (node (ref "U2") (pin "G7") (pinfunction "VDD3_G7") (pintype "power_in"))
      (node (ref "U2") (pin "H2") (pinfunction "VDDQ8_H2") (pintype "power_in"))
      (node (ref "U2") (pin "H9") (pinfunction "VDDQ9_H9") (pintype "power_in"))
      (node (ref "U2") (pin "K2") (pinfunction "VDD4_K2") (pintype "power_in"))
      (node (ref "U2") (pin "K8") (pinfunction "VDD5_K8") (pintype "power_in"))
      (node (ref "U2") (pin "N1") (pinfunction "VDD6_N1") (pintype "power_in"))
      (node (ref "U2") (pin "N9") (pinfunction "VDD7_N9") (pintype "power_in"))
      (node (ref "U2") (pin "R1") (pinfunction "VDD8_R1") (pintype "power_in"))
      (node (ref "U2") (pin "R9") (pinfunction "VDD9_R9") (pintype "power_in"))
      (node (ref "U3") (pin "A1") (pinfunction "VDDQ1_A1") (pintype "power_in"))
      (node (ref "U3") (pin "A8") (pinfunction "VDDQ2_A8") (pintype "power_in"))
      (node (ref "U3") (pin "B2") (pinfunction "VDD1_B2") (pintype "power_in"))
      (node (ref "U3") (pin "C1") (pinfunction "VDDQ3_C1") (pintype "power_in"))
      (node (ref "U3") (pin "C9") (pinfunction "VDDQ4_C9") (pintype "power_in"))
      (node (ref "U3") (pin "D2") (pinfunction "VDDQ5_D2") (pintype "power_in"))
      (node (ref "U3") (pin "D9") (pinfunction "VDD2_D9") (pintype "power_in"))
      (node (ref "U3") (pin "E9") (pinfunction "VDDQ6_E9") (pintype "power_in"))
      (node (ref "U3") (pin "F1") (pinfunction "VDDQ7_F1") (pintype "power_in"))
      (node (ref "U3") (pin "G7") (pinfunction "VDD3_G7") (pintype "power_in"))
      (node (ref "U3") (pin "H2") (pinfunction "VDDQ8_H2") (pintype "power_in"))
      (node (ref "U3") (pin "H9") (pinfunction "VDDQ9_H9") (pintype "power_in"))
      (node (ref "U3") (pin "K2") (pinfunction "VDD4_K2") (pintype "power_in"))
      (node (ref "U3") (pin "K8") (pinfunction "VDD5_K8") (pintype "power_in"))
      (node (ref "U3") (pin "N1") (pinfunction "VDD6_N1") (pintype "power_in"))
      (node (ref "U3") (pin "N9") (pinfunction "VDD7_N9") (pintype "power_in"))
      (node (ref "U3") (pin "R1") (pinfunction "VDD8_R1") (pintype "power_in"))
      (node (ref "U3") (pin "R9") (pinfunction "VDD9_R9") (pintype "power_in"))
      (node (ref "U4") (pin "A1") (pinfunction "VDDQ1_A1") (pintype "power_in"))
      (node (ref "U4") (pin "A8") (pinfunction "VDDQ2_A8") (pintype "power_in"))
      (node (ref "U4") (pin "B2") (pinfunction "VDD1_B2") (pintype "power_in"))
      (node (ref "U4") (pin "C1") (pinfunction "VDDQ3_C1") (pintype "power_in"))
      (node (ref "U4") (pin "C9") (pinfunction "VDDQ4_C9") (pintype "power_in"))
      (node (ref "U4") (pin "D2") (pinfunction "VDDQ5_D2") (pintype "power_in"))
      (node (ref "U4") (pin "D9") (pinfunction "VDD2_D9") (pintype "power_in"))
      (node (ref "U4") (pin "E9") (pinfunction "VDDQ6_E9") (pintype "power_in"))
      (node (ref "U4") (pin "F1") (pinfunction "VDDQ7_F1") (pintype "power_in"))
      (node (ref "U4") (pin "G7") (pinfunction "VDD3_G7") (pintype "power_in"))
      (node (ref "U4") (pin "H2") (pinfunction "VDDQ8_H2") (pintype "power_in"))
      (node (ref "U4") (pin "H9") (pinfunction "VDDQ9_H9") (pintype "power_in"))
      (node (ref "U4") (pin "K2") (pinfunction "VDD4_K2") (pintype "power_in"))
      (node (ref "U4") (pin "K8") (pinfunction "VDD5_K8") (pintype "power_in"))
      (node (ref "U4") (pin "N1") (pinfunction "VDD6_N1") (pintype "power_in"))
      (node (ref "U4") (pin "N9") (pinfunction "VDD7_N9") (pintype "power_in"))
      (node (ref "U4") (pin "R1") (pinfunction "VDD8_R1") (pintype "power_in"))
      (node (ref "U4") (pin "R9") (pinfunction "VDD9_R9") (pintype "power_in"))
      (node (ref "U5") (pin "A1") (pinfunction "VDDQ1_A1") (pintype "power_in"))
      (node (ref "U5") (pin "A8") (pinfunction "VDDQ2_A8") (pintype "power_in"))
      (node (ref "U5") (pin "B2") (pinfunction "VDD1_B2") (pintype "power_in"))
      (node (ref "U5") (pin "C1") (pinfunction "VDDQ3_C1") (pintype "power_in"))
      (node (ref "U5") (pin "C9") (pinfunction "VDDQ4_C9") (pintype "power_in"))
      (node (ref "U5") (pin "D2") (pinfunction "VDDQ5_D2") (pintype "power_in"))
      (node (ref "U5") (pin "D9") (pinfunction "VDD2_D9") (pintype "power_in"))
      (node (ref "U5") (pin "E9") (pinfunction "VDDQ6_E9") (pintype "power_in"))
      (node (ref "U5") (pin "F1") (pinfunction "VDDQ7_F1") (pintype "power_in"))
      (node (ref "U5") (pin "G7") (pinfunction "VDD3_G7") (pintype "power_in"))
      (node (ref "U5") (pin "H2") (pinfunction "VDDQ8_H2") (pintype "power_in"))
      (node (ref "U5") (pin "H9") (pinfunction "VDDQ9_H9") (pintype "power_in"))
      (node (ref "U5") (pin "K2") (pinfunction "VDD4_K2") (pintype "power_in"))
      (node (ref "U5") (pin "K8") (pinfunction "VDD5_K8") (pintype "power_in"))
      (node (ref "U5") (pin "N1") (pinfunction "VDD6_N1") (pintype "power_in"))
      (node (ref "U5") (pin "N9") (pinfunction "VDD7_N9") (pintype "power_in"))
      (node (ref "U5") (pin "R1") (pinfunction "VDD8_R1") (pintype "power_in"))
      (node (ref "U5") (pin "R9") (pinfunction "VDD9_R9") (pintype "power_in"))
    )
    (net (code "2") (name "+DDR_VREF") (class "Default")
      (node (ref "C10") (pin "1") (pinfunction "1_1") (pintype "passive"))
      (node (ref "C11") (pin "1") (pinfunction "1_1") (pintype "passive"))
      (node (ref "C18") (pin "2") (pinfunction "2_2") (pintype "passive"))
      (node (ref "C20") (pin "1") (pinfunction "1_1") (pintype "passive"))
      (node (ref "C3") (pin "1") (pinfunction "1_1") (pintype "passive"))
      (node (ref "C4") (pin "1") (pinfunction "1_1") (pintype "passive"))
      (node (ref "C5") (pin "1") (pinfunction "1_1") (pintype "passive"))
      (node (ref "C6") (pin "1") (pinfunction "1_1") (pintype "passive"))
      (node (ref "C7") (pin "1") (pinfunction "1_1") (pintype "passive"))
      (node (ref "C8") (pin "1") (pinfunction "1_1") (pintype "passive"))
      (node (ref "C9") (pin "1") (pinfunction "1_1") (pintype "passive"))
      (node (ref "R11") (pin "1") (pinfunction "1_1") (pintype "passive"))
      (node (ref "R12") (pin "2") (pinfunction "2_2") (pintype "passive"))
      (node (ref "U1") (pin "AC2") (pinfunction "DRAM_VREF_AC2") (pintype "power_in"))
      (node (ref "U2") (pin "H1") (pinfunction "VREFDQ_H1") (pintype "input"))
      (node (ref "U2") (pin "M8") (pinfunction "VREFCA_M8") (pintype "input"))
      (node (ref "U3") (pin "H1") (pinfunction "VREFDQ_H1") (pintype "input"))
      (node (ref "U3") (pin "M8") (pinfunction "VREFCA_M8") (pintype "input"))
      (node (ref "U4") (pin "H1") (pinfunction "VREFDQ_H1") (pintype "input"))
      (node (ref "U4") (pin "M8") (pinfunction "VREFCA_M8") (pintype "input"))
      (node (ref "U5") (pin "H1") (pinfunction "VREFDQ_H1") (pintype "input"))
      (node (ref "U5") (pin "M8") (pinfunction "VREFCA_M8") (pintype "input"))
    )
    (net (code "3") (name "/DRAM0_ZQ") (class "Default")
      (node (ref "R4") (pin "2") (pinfunction "2_2") (pintype "passive"))
      (node (ref "U2") (pin "L8") (pinfunction "ZQ_L8") (pintype "passive"))
    )
    (net (code "4") (name "/DRAM1_ZQ") (class "Default")
      (node (ref "R5") (pin "2") (pinfunction "2_2") (pintype "passive"))
      (node (ref "U3") (pin "L8") (pinfunction "ZQ_L8") (pintype "passive"))
    )
    (net (code "5") (name "/DRAM2_ZQ") (class "Default")
      (node (ref "R8") (pin "2") (pinfunction "2_2") (pintype "passive"))
      (node (ref "U4") (pin "L8") (pinfunction "ZQ_L8") (pintype "passive"))
    )
    (net (code "6") (name "/DRAM3_ZQ") (class "Default")
      (node (ref "R9") (pin "2") (pinfunction "2_2") (pintype "passive"))
      (node (ref "U5") (pin "L8") (pinfunction "ZQ_L8") (pintype "passive"))
    )
    (net (code "7") (name "/DRAM_A0") (class "Default")
      (node (ref "U1") (pin "AC14") (pinfunction "DRAM_A0_AC14") (pintype "output"))
      (node (ref "U2") (pin "N3") (pinfunction "A0_N3") (pintype "input"))
      (node (ref "U3") (pin "N3") (pinfunction "A0_N3") (pintype "input"))
      (node (ref "U4") (pin "N3") (pinfunction "A0_N3") (pintype "input"))
      (node (ref "U5") (pin "N3") (pinfunction "A0_N3") (pintype "input"))
    )
    (net (code "8") (name "/DRAM_A1") (class "Default")
      (node (ref "U1") (pin "AB14") (pinfunction "DRAM_A1_AB14") (pintype "output"))
      (node (ref "U2") (pin "P7") (pinfunction "A1_P7") (pintype "input"))
      (node (ref "U3") (pin "P7") (pinfunction "A1_P7") (pintype "input"))
      (node (ref "U4") (pin "P7") (pinfunction "A1_P7") (pintype "input"))
      (node (ref "U5") (pin "P7") (pinfunction "A1_P7") (pintype "input"))
    )
    (net (code "9") (name "/DRAM_A2") (class "Default")
      (node (ref "U1") (pin "AA14") (pinfunction "DRAM_A2_AA14") (pintype "output"))
      (node (ref "U2") (pin "P3") (pinfunction "A2_P3") (pintype "input"))
      (node (ref "U3") (pin "P3") (pinfunction "A2_P3") (pintype "input"))
      (node (ref "U4") (pin "P3") (pinfunction "A2_P3") (pintype "input"))
      (node (ref "U5") (pin "P3") (pinfunction "A2_P3") (pintype "input"))
    )
    (net (code "10") (name "/DRAM_A3") (class "Default")
      (node (ref "U1") (pin "Y14") (pinfunction "DRAM_A3_Y14") (pintype "output"))
      (node (ref "U2") (pin "N2") (pinfunction "A3_N2") (pintype "input"))
      (node (ref "U3") (pin "N2") (pinfunction "A3_N2") (pintype "input"))
      (node (ref "U4") (pin "N2") (pinfunction "A3_N2") (pintype "input"))
      (node (ref "U5") (pin "N2") (pinfunction "A3_N2") (pintype "input"))
    )
    (net (code "11") (name "/DRAM_A4") (class "Default")
      (node (ref "U1") (pin "W14") (pinfunction "DRAM_A4_W14") (pintype "output"))
      (node (ref "U2") (pin "P8") (pinfunction "A4_P8") (pintype "input"))
      (node (ref "U3") (pin "P8") (pinfunction "A4_P8") (pintype "input"))
      (node (ref "U4") (pin "P8") (pinfunction "A4_P8") (pintype "input"))
      (node (ref "U5") (pin "P8") (pinfunction "A4_P8") (pintype "input"))
    )
    (net (code "12") (name "/DRAM_A5") (class "Default")
      (node (ref "U1") (pin "AE13") (pinfunction "DRAM_A5_AE13") (pintype "output"))
      (node (ref "U2") (pin "P2") (pinfunction "A5_P2") (pintype "input"))
      (node (ref "U3") (pin "P2") (pinfunction "A5_P2") (pintype "input"))
      (node (ref "U4") (pin "P2") (pinfunction "A5_P2") (pintype "input"))
      (node (ref "U5") (pin "P2") (pinfunction "A5_P2") (pintype "input"))
    )
    (net (code "13") (name "/DRAM_A6") (class "Default")
      (node (ref "U1") (pin "AC13") (pinfunction "DRAM_A6_AC13") (pintype "output"))
      (node (ref "U2") (pin "R8") (pinfunction "A6_R8") (pintype "input"))
      (node (ref "U3") (pin "R8") (pinfunction "A6_R8") (pintype "input"))
      (node (ref "U4") (pin "R8") (pinfunction "A6_R8") (pintype "input"))
      (node (ref "U5") (pin "R8") (pinfunction "A6_R8") (pintype "input"))
    )
    (net (code "14") (name "/DRAM_A7") (class "Default")
      (node (ref "U1") (pin "Y13") (pinfunction "DRAM_A7_Y13") (pintype "output"))
      (node (ref "U2") (pin "R2") (pinfunction "A7_R2") (pintype "input"))
      (node (ref "U3") (pin "R2") (pinfunction "A7_R2") (pintype "input"))
      (node (ref "U4") (pin "R2") (pinfunction "A7_R2") (pintype "input"))
      (node (ref "U5") (pin "R2") (pinfunction "A7_R2") (pintype "input"))
    )
    (net (code "15") (name "/DRAM_A8") (class "Default")
      (node (ref "U1") (pin "AB13") (pinfunction "DRAM_A8_AB13") (pintype "output"))
      (node (ref "U2") (pin "T8") (pinfunction "A8_T8") (pintype "input"))
      (node (ref "U3") (pin "T8") (pinfunction "A8_T8") (pintype "input"))
      (node (ref "U4") (pin "T8") (pinfunction "A8_T8") (pintype "input"))
      (node (ref "U5") (pin "T8") (pinfunction "A8_T8") (pintype "input"))
    )
    (net (code "16") (name "/DRAM_A9") (class "Default")
      (node (ref "U1") (pin "AE12") (pinfunction "DRAM_A9_AE12") (pintype "output"))
      (node (ref "U2") (pin "R3") (pinfunction "A9_R3") (pintype "input"))
      (node (ref "U3") (pin "R3") (pinfunction "A9_R3") (pintype "input"))
      (node (ref "U4") (pin "R3") (pinfunction "A9_R3") (pintype "input"))
      (node (ref "U5") (pin "R3") (pinfunction "A9_R3") (pintype "input"))
    )
    (net (code "17") (name "/DRAM_A10") (class "Default")
      (node (ref "U1") (pin "AA15") (pinfunction "DRAM_A10_AA15") (pintype "output"))
      (node (ref "U2") (pin "L7") (pinfunction "A10/AP_L7") (pintype "input"))
      (node (ref "U3") (pin "L7") (pinfunction "A10/AP_L7") (pintype "input"))
      (node (ref "U4") (pin "L7") (pinfunction "A10/AP_L7") (pintype "input"))
      (node (ref "U5") (pin "L7") (pinfunction "A10/AP_L7") (pintype "input"))
    )
    (net (code "18") (name "/DRAM_A11") (class "Default")
      (node (ref "U1") (pin "AC12") (pinfunction "DRAM_A11_AC12") (pintype "output"))
      (node (ref "U2") (pin "R7") (pinfunction "A11_R7") (pintype "input"))
      (node (ref "U3") (pin "R7") (pinfunction "A11_R7") (pintype "input"))
      (node (ref "U4") (pin "R7") (pinfunction "A11_R7") (pintype "input"))
      (node (ref "U5") (pin "R7") (pinfunction "A11_R7") (pintype "input"))
    )
    (net (code "19") (name "/DRAM_A12") (class "Default")
      (node (ref "U1") (pin "AD12") (pinfunction "DRAM_A12_AD12") (pintype "output"))
      (node (ref "U2") (pin "N7") (pinfunction "A12/~{BC}_N7") (pintype "input"))
      (node (ref "U3") (pin "N7") (pinfunction "A12/~{BC}_N7") (pintype "input"))
      (node (ref "U4") (pin "N7") (pinfunction "A12/~{BC}_N7") (pintype "input"))
      (node (ref "U5") (pin "N7") (pinfunction "A12/~{BC}_N7") (pintype "input"))
    )
    (net (code "20") (name "/DRAM_A13") (class "Default")
      (node (ref "U1") (pin "AC17") (pinfunction "DRAM_A13_AC17") (pintype "output"))
      (node (ref "U2") (pin "T3") (pinfunction "A13_T3") (pintype "input"))
      (node (ref "U3") (pin "T3") (pinfunction "A13_T3") (pintype "input"))
      (node (ref "U4") (pin "T3") (pinfunction "A13_T3") (pintype "input"))
      (node (ref "U5") (pin "T3") (pinfunction "A13_T3") (pintype "input"))
    )
    (net (code "21") (name "/DRAM_A14") (class "Default")
      (node (ref "U1") (pin "AA12") (pinfunction "DRAM_A14_AA12") (pintype "output"))
      (node (ref "U2") (pin "T7") (pinfunction "NC_T7_T7") (pintype "passive"))
      (node (ref "U3") (pin "T7") (pinfunction "NC_T7_T7") (pintype "passive"))
      (node (ref "U4") (pin "T7") (pinfunction "NC_T7_T7") (pintype "passive"))
      (node (ref "U5") (pin "T7") (pinfunction "NC_T7_T7") (pintype "passive"))
    )
    (net (code "22") (name "/DRAM_A15") (class "Default")
      (node (ref "U1") (pin "Y12") (pinfunction "DRAM_A15_Y12") (pintype "output"))
      (node (ref "U2") (pin "M7") (pinfunction "NC_M7_M7") (pintype "passive"))
      (node (ref "U3") (pin "M7") (pinfunction "NC_M7_M7") (pintype "passive"))
      (node (ref "U4") (pin "M7") (pinfunction "NC_M7_M7") (pintype "passive"))
      (node (ref "U5") (pin "M7") (pinfunction "NC_M7_M7") (pintype "passive"))
    )
    (net (code "24") (name "/DRAM_CAS_B") (class "Default")
      (node (ref "U1") (pin "AE16") (pinfunction "DRAM_CAS_AE16") (pintype "output"))
      (node (ref "U2") (pin "K3") (pinfunction "~{CAS}_K3") (pintype "input"))
      (node (ref "U3") (pin "K3") (pinfunction "~{CAS}_K3") (pintype "input"))
      (node (ref "U4") (pin "K3") (pinfunction "~{CAS}_K3") (pintype "input"))
      (node (ref "U5") (pin "K3") (pinfunction "~{CAS}_K3") (pintype "input"))
    )
    (net (code "25") (name "/DRAM_CLK0_N") (class "Default")
      (node (ref "R2") (pin "1") (pinfunction "1_1") (pintype "passive"))
      (node (ref "U1") (pin "AE15") (pinfunction "~{DRAM_SDCLK_0}_AE15") (pintype "output"))
      (node (ref "U4") (pin "K7") (pinfunction "~{CK}_K7") (pintype "input"))
      (node (ref "U5") (pin "K7") (pinfunction "~{CK}_K7") (pintype "input"))
    )
    (net (code "26") (name "/DRAM_CLK0_P") (class "Default")
      (node (ref "R2") (pin "2") (pinfunction "2_2") (pintype "passive"))
      (node (ref "U1") (pin "AD15") (pinfunction "DRAM_SDCLK_0_AD15") (pintype "output"))
      (node (ref "U4") (pin "J7") (pinfunction "CK_J7") (pintype "input"))
      (node (ref "U5") (pin "J7") (pinfunction "CK_J7") (pintype "input"))
    )
    (net (code "27") (name "/DRAM_CLK1_N") (class "Default")
      (node (ref "R3") (pin "1") (pinfunction "1_1") (pintype "passive"))
      (node (ref "U1") (pin "AE14") (pinfunction "~{DRAM_SDCLK_1}_AE14") (pintype "output"))
      (node (ref "U2") (pin "K7") (pinfunction "~{CK}_K7") (pintype "input"))
      (node (ref "U3") (pin "K7") (pinfunction "~{CK}_K7") (pintype "input"))
    )
    (net (code "28") (name "/DRAM_CLK1_P") (class "Default")
      (node (ref "R3") (pin "2") (pinfunction "2_2") (pintype "passive"))
      (node (ref "U1") (pin "AD14") (pinfunction "DRAM_SDCLK_1_AD14") (pintype "output"))
      (node (ref "U2") (pin "J7") (pinfunction "CK_J7") (pintype "input"))
      (node (ref "U3") (pin "J7") (pinfunction "CK_J7") (pintype "input"))
    )
    (net (code "29") (name "/DRAM_CS0_B") (class "Default")
      (node (ref "U1") (pin "Y16") (pinfunction "DRAM_CS0_Y16") (pintype "output"))
      (node (ref "U2") (pin "L2") (pinfunction "~{CS}_L2") (pintype "input"))
      (node (ref "U3") (pin "L2") (pinfunction "~{CS}_L2") (pintype "input"))
      (node (ref "U4") (pin "L2") (pinfunction "~{CS}_L2") (pintype "input"))
      (node (ref "U5") (pin "L2") (pinfunction "~{CS}_L2") (pintype "input"))
    )
    (net (code "30") (name "/DRAM_D0") (class "Default")
      (node (ref "U1") (pin "AD2") (pinfunction "DRAM_D0_AD2") (pintype "bidirectional"))
      (node (ref "U2") (pin "D7") (pinfunction "DQ8_D7") (pintype "bidirectional"))
    )
    (net (code "31") (name "/DRAM_D1") (class "Default")
      (node (ref "U1") (pin "AE2") (pinfunction "DRAM_D1_AE2") (pintype "bidirectional"))
      (node (ref "U2") (pin "B8") (pinfunction "DQ14_B8") (pintype "bidirectional"))
    )
    (net (code "32") (name "/DRAM_D2") (class "Default")
      (node (ref "U1") (pin "AC4") (pinfunction "DRAM_D2_AC4") (pintype "bidirectional"))
      (node (ref "U2") (pin "C8") (pinfunction "DQ10_C8") (pintype "bidirectional"))
    )
    (net (code "33") (name "/DRAM_D3") (class "Default")
      (node (ref "U1") (pin "AA5") (pinfunction "DRAM_D3_AA5") (pintype "bidirectional"))
      (node (ref "U2") (pin "A3") (pinfunction "DQ15_A3") (pintype "bidirectional"))
    )
    (net (code "34") (name "/DRAM_D4") (class "Default")
      (node (ref "U1") (pin "AC1") (pinfunction "DRAM_D4_AC1") (pintype "bidirectional"))
      (node (ref "U2") (pin "C2") (pinfunction "DQ11_C2") (pintype "bidirectional"))
    )
    (net (code "35") (name "/DRAM_D5") (class "Default")
      (node (ref "U1") (pin "AD1") (pinfunction "DRAM_D5_AD1") (pintype "bidirectional"))
      (node (ref "U2") (pin "C3") (pinfunction "DQ9_C3") (pintype "bidirectional"))
    )
    (net (code "36") (name "/DRAM_D6") (class "Default")
      (node (ref "U1") (pin "AB4") (pinfunction "DRAM_D6_AB4") (pintype "bidirectional"))
      (node (ref "U2") (pin "A2") (pinfunction "DQ13_A2") (pintype "bidirectional"))
    )
    (net (code "37") (name "/DRAM_D7") (class "Default")
      (node (ref "U1") (pin "AE4") (pinfunction "DRAM_D7_AE4") (pintype "bidirectional"))
      (node (ref "U2") (pin "A7") (pinfunction "DQ12_A7") (pintype "bidirectional"))
    )
    (net (code "38") (name "/DRAM_D8") (class "Default")
      (node (ref "U1") (pin "AD5") (pinfunction "DRAM_D8_AD5") (pintype "bidirectional"))
      (node (ref "U2") (pin "E3") (pinfunction "DQ0_E3") (pintype "bidirectional"))
    )
    (net (code "39") (name "/DRAM_D9") (class "Default")
      (node (ref "U1") (pin "AE5") (pinfunction "DRAM_D9_AE5") (pintype "bidirectional"))
      (node (ref "U2") (pin "F7") (pinfunction "DQ1_F7") (pintype "bidirectional"))
    )
    (net (code "40") (name "/DRAM_D10") (class "Default")
      (node (ref "U1") (pin "AA6") (pinfunction "DRAM_D10_AA6") (pintype "bidirectional"))
      (node (ref "U2") (pin "G2") (pinfunction "DQ6_G2") (pintype "bidirectional"))
    )
    (net (code "41") (name "/DRAM_D11") (class "Default")
      (node (ref "U1") (pin "AE7") (pinfunction "DRAM_D11_AE7") (pintype "bidirectional"))
      (node (ref "U2") (pin "H7") (pinfunction "DQ7_H7") (pintype "bidirectional"))
    )
    (net (code "42") (name "/DRAM_D12") (class "Default")
      (node (ref "U1") (pin "AB5") (pinfunction "DRAM_D12_AB5") (pintype "bidirectional"))
      (node (ref "U2") (pin "H3") (pinfunction "DQ4_H3") (pintype "bidirectional"))
    )
    (net (code "43") (name "/DRAM_D13") (class "Default")
      (node (ref "U1") (pin "AC5") (pinfunction "DRAM_D13_AC5") (pintype "bidirectional"))
      (node (ref "U2") (pin "F2") (pinfunction "DQ2_F2") (pintype "bidirectional"))
    )
    (net (code "44") (name "/DRAM_D14") (class "Default")
      (node (ref "U1") (pin "AB6") (pinfunction "DRAM_D14_AB6") (pintype "bidirectional"))
      (node (ref "U2") (pin "F8") (pinfunction "DQ3_F8") (pintype "bidirectional"))
    )
    (net (code "45") (name "/DRAM_D15") (class "Default")
      (node (ref "U1") (pin "AC7") (pinfunction "DRAM_D15_AC7") (pintype "bidirectional"))
      (node (ref "U2") (pin "H8") (pinfunction "DQ5_H8") (pintype "bidirectional"))
    )
    (net (code "46") (name "/DRAM_D16") (class "Default")
      (node (ref "U1") (pin "AB7") (pinfunction "DRAM_D16_AB7") (pintype "bidirectional"))
      (node (ref "U3") (pin "E3") (pinfunction "DQ0_E3") (pintype "bidirectional"))
    )
    (net (code "47") (name "/DRAM_D17") (class "Default")
      (node (ref "U1") (pin "AA8") (pinfunction "DRAM_D17_AA8") (pintype "bidirectional"))
      (node (ref "U3") (pin "F8") (pinfunction "DQ3_F8") (pintype "bidirectional"))
    )
    (net (code "48") (name "/DRAM_D18") (class "Default")
      (node (ref "U1") (pin "AB9") (pinfunction "DRAM_D18_AB9") (pintype "bidirectional"))
      (node (ref "U3") (pin "H7") (pinfunction "DQ7_H7") (pintype "bidirectional"))
    )
    (net (code "49") (name "/DRAM_D19") (class "Default")
      (node (ref "U1") (pin "Y9") (pinfunction "DRAM_D19_Y9") (pintype "bidirectional"))
      (node (ref "U3") (pin "H3") (pinfunction "DQ4_H3") (pintype "bidirectional"))
    )
    (net (code "50") (name "/DRAM_D20") (class "Default")
      (node (ref "U1") (pin "Y7") (pinfunction "DRAM_D20_Y7") (pintype "bidirectional"))
      (node (ref "U3") (pin "H8") (pinfunction "DQ5_H8") (pintype "bidirectional"))
    )
    (net (code "51") (name "/DRAM_D21") (class "Default")
      (node (ref "U1") (pin "Y8") (pinfunction "DRAM_D21_Y8") (pintype "bidirectional"))
      (node (ref "U3") (pin "G2") (pinfunction "DQ6_G2") (pintype "bidirectional"))
    )
    (net (code "52") (name "/DRAM_D22") (class "Default")
      (node (ref "U1") (pin "AC8") (pinfunction "DRAM_D22_AC8") (pintype "bidirectional"))
      (node (ref "U3") (pin "F7") (pinfunction "DQ1_F7") (pintype "bidirectional"))
    )
    (net (code "53") (name "/DRAM_D23") (class "Default")
      (node (ref "U1") (pin "AA9") (pinfunction "DRAM_D23_AA9") (pintype "bidirectional"))
      (node (ref "U3") (pin "F2") (pinfunction "DQ2_F2") (pintype "bidirectional"))
    )
    (net (code "54") (name "/DRAM_D24") (class "Default")
      (node (ref "U1") (pin "AE9") (pinfunction "DRAM_D24_AE9") (pintype "bidirectional"))
      (node (ref "U3") (pin "D7") (pinfunction "DQ8_D7") (pintype "bidirectional"))
    )
    (net (code "55") (name "/DRAM_D25") (class "Default")
      (node (ref "U1") (pin "Y10") (pinfunction "DRAM_D25_Y10") (pintype "bidirectional"))
      (node (ref "U3") (pin "A7") (pinfunction "DQ12_A7") (pintype "bidirectional"))
    )
    (net (code "56") (name "/DRAM_D26") (class "Default")
      (node (ref "U1") (pin "AE11") (pinfunction "DRAM_D26_AE11") (pintype "bidirectional"))
      (node (ref "U3") (pin "C3") (pinfunction "DQ9_C3") (pintype "bidirectional"))
    )
    (net (code "57") (name "/DRAM_D27") (class "Default")
      (node (ref "U1") (pin "AB11") (pinfunction "DRAM_D27_AB11") (pintype "bidirectional"))
      (node (ref "U3") (pin "C2") (pinfunction "DQ11_C2") (pintype "bidirectional"))
    )
    (net (code "58") (name "/DRAM_D28") (class "Default")
      (node (ref "U1") (pin "AC9") (pinfunction "DRAM_D28_AC9") (pintype "bidirectional"))
      (node (ref "U3") (pin "C8") (pinfunction "DQ10_C8") (pintype "bidirectional"))
    )
    (net (code "59") (name "/DRAM_D29") (class "Default")
      (node (ref "U1") (pin "AD9") (pinfunction "DRAM_D29_AD9") (pintype "bidirectional"))
      (node (ref "U3") (pin "B8") (pinfunction "DQ14_B8") (pintype "bidirectional"))
    )
    (net (code "60") (name "/DRAM_D30") (class "Default")
      (node (ref "U1") (pin "AD11") (pinfunction "DRAM_D30_AD11") (pintype "bidirectional"))
      (node (ref "U3") (pin "A2") (pinfunction "DQ13_A2") (pintype "bidirectional"))
    )
    (net (code "61") (name "/DRAM_D31") (class "Default")
      (node (ref "U1") (pin "AC11") (pinfunction "DRAM_D31_AC11") (pintype "bidirectional"))
      (node (ref "U3") (pin "A3") (pinfunction "DQ15_A3") (pintype "bidirectional"))
    )
    (net (code "62") (name "/DRAM_D32") (class "Default")
      (node (ref "U1") (pin "AA17") (pinfunction "DRAM_D32_AA17") (pintype "bidirectional"))
      (node (ref "U5") (pin "E3") (pinfunction "DQ0_E3") (pintype "bidirectional"))
    )
    (net (code "63") (name "/DRAM_D33") (class "Default")
      (node (ref "U1") (pin "AA18") (pinfunction "DRAM_D33_AA18") (pintype "bidirectional"))
      (node (ref "U5") (pin "G2") (pinfunction "DQ6_G2") (pintype "bidirectional"))
    )
    (net (code "64") (name "/DRAM_D34") (class "Default")
      (node (ref "U1") (pin "AC18") (pinfunction "DRAM_D34_AC18") (pintype "bidirectional"))
      (node (ref "U5") (pin "F8") (pinfunction "DQ3_F8") (pintype "bidirectional"))
    )
    (net (code "65") (name "/DRAM_D35") (class "Default")
      (node (ref "U1") (pin "AE19") (pinfunction "DRAM_D35_AE19") (pintype "bidirectional"))
      (node (ref "U5") (pin "H7") (pinfunction "DQ7_H7") (pintype "bidirectional"))
    )
    (net (code "66") (name "/DRAM_D36") (class "Default")
      (node (ref "U1") (pin "Y17") (pinfunction "DRAM_D36_Y17") (pintype "bidirectional"))
      (node (ref "U5") (pin "H3") (pinfunction "DQ4_H3") (pintype "bidirectional"))
    )
    (net (code "67") (name "/DRAM_D37") (class "Default")
      (node (ref "U1") (pin "Y18") (pinfunction "DRAM_D37_Y18") (pintype "bidirectional"))
      (node (ref "U5") (pin "F2") (pinfunction "DQ2_F2") (pintype "bidirectional"))
    )
    (net (code "68") (name "/DRAM_D38") (class "Default")
      (node (ref "U1") (pin "AB19") (pinfunction "DRAM_D38_AB19") (pintype "bidirectional"))
      (node (ref "U5") (pin "H8") (pinfunction "DQ5_H8") (pintype "bidirectional"))
    )
    (net (code "69") (name "/DRAM_D39") (class "Default")
      (node (ref "U1") (pin "AC19") (pinfunction "DRAM_D39_AC19") (pintype "bidirectional"))
      (node (ref "U5") (pin "F7") (pinfunction "DQ1_F7") (pintype "bidirectional"))
    )
    (net (code "70") (name "/DRAM_D40") (class "Default")
      (node (ref "U1") (pin "Y19") (pinfunction "DRAM_D40_Y19") (pintype "bidirectional"))
      (node (ref "U5") (pin "D7") (pinfunction "DQ8_D7") (pintype "bidirectional"))
    )
    (net (code "71") (name "/DRAM_D41") (class "Default")
      (node (ref "U1") (pin "AB20") (pinfunction "DRAM_D41_AB20") (pintype "bidirectional"))
      (node (ref "U5") (pin "B8") (pinfunction "DQ14_B8") (pintype "bidirectional"))
    )
    (net (code "72") (name "/DRAM_D42") (class "Default")
      (node (ref "U1") (pin "AB21") (pinfunction "DRAM_D42_AB21") (pintype "bidirectional"))
      (node (ref "U5") (pin "C2") (pinfunction "DQ11_C2") (pintype "bidirectional"))
    )
    (net (code "73") (name "/DRAM_D43") (class "Default")
      (node (ref "U1") (pin "AD21") (pinfunction "DRAM_D43_AD21") (pintype "bidirectional"))
      (node (ref "U5") (pin "A7") (pinfunction "DQ12_A7") (pintype "bidirectional"))
    )
    (net (code "74") (name "/DRAM_D44") (class "Default")
      (node (ref "U1") (pin "Y20") (pinfunction "DRAM_D44_Y20") (pintype "bidirectional"))
      (node (ref "U5") (pin "A2") (pinfunction "DQ13_A2") (pintype "bidirectional"))
    )
    (net (code "75") (name "/DRAM_D45") (class "Default")
      (node (ref "U1") (pin "AA20") (pinfunction "DRAM_D45_AA20") (pintype "bidirectional"))
      (node (ref "U5") (pin "C8") (pinfunction "DQ10_C8") (pintype "bidirectional"))
    )
    (net (code "76") (name "/DRAM_D46") (class "Default")
      (node (ref "U1") (pin "AE21") (pinfunction "DRAM_D46_AE21") (pintype "bidirectional"))
      (node (ref "U5") (pin "A3") (pinfunction "DQ15_A3") (pintype "bidirectional"))
    )
    (net (code "77") (name "/DRAM_D47") (class "Default")
      (node (ref "U1") (pin "AC21") (pinfunction "DRAM_D47_AC21") (pintype "bidirectional"))
      (node (ref "U5") (pin "C3") (pinfunction "DQ9_C3") (pintype "bidirectional"))
    )
    (net (code "78") (name "/DRAM_D48") (class "Default")
      (node (ref "U1") (pin "AC22") (pinfunction "DRAM_D48_AC22") (pintype "bidirectional"))
      (node (ref "U4") (pin "D7") (pinfunction "DQ8_D7") (pintype "bidirectional"))
    )
    (net (code "79") (name "/DRAM_D49") (class "Default")
      (node (ref "U1") (pin "AE22") (pinfunction "DRAM_D49_AE22") (pintype "bidirectional"))
      (node (ref "U4") (pin "C2") (pinfunction "DQ11_C2") (pintype "bidirectional"))
    )
    (net (code "80") (name "/DRAM_D50") (class "Default")
      (node (ref "U1") (pin "AE24") (pinfunction "DRAM_D50_AE24") (pintype "bidirectional"))
      (node (ref "U4") (pin "C3") (pinfunction "DQ9_C3") (pintype "bidirectional"))
    )
    (net (code "81") (name "/DRAM_D51") (class "Default")
      (node (ref "U1") (pin "AC24") (pinfunction "DRAM_D51_AC24") (pintype "bidirectional"))
      (node (ref "U4") (pin "B8") (pinfunction "DQ14_B8") (pintype "bidirectional"))
    )
    (net (code "82") (name "/DRAM_D52") (class "Default")
      (node (ref "U1") (pin "AB22") (pinfunction "DRAM_D52_AB22") (pintype "bidirectional"))
      (node (ref "U4") (pin "A7") (pinfunction "DQ12_A7") (pintype "bidirectional"))
    )
    (net (code "83") (name "/DRAM_D53") (class "Default")
      (node (ref "U1") (pin "AC23") (pinfunction "DRAM_D53_AC23") (pintype "bidirectional"))
      (node (ref "U4") (pin "C8") (pinfunction "DQ10_C8") (pintype "bidirectional"))
    )
    (net (code "84") (name "/DRAM_D54") (class "Default")
      (node (ref "U1") (pin "AD25") (pinfunction "DRAM_D54_AD25") (pintype "bidirectional"))
      (node (ref "U4") (pin "A3") (pinfunction "DQ15_A3") (pintype "bidirectional"))
    )
    (net (code "85") (name "/DRAM_D55") (class "Default")
      (node (ref "U1") (pin "AC25") (pinfunction "DRAM_D55_AC25") (pintype "bidirectional"))
      (node (ref "U4") (pin "A2") (pinfunction "DQ13_A2") (pintype "bidirectional"))
    )
    (net (code "86") (name "/DRAM_D56") (class "Default")
      (node (ref "U1") (pin "AB25") (pinfunction "DRAM_D56_AB25") (pintype "bidirectional"))
      (node (ref "U4") (pin "E3") (pinfunction "DQ0_E3") (pintype "bidirectional"))
    )
    (net (code "87") (name "/DRAM_D57") (class "Default")
      (node (ref "U1") (pin "AA21") (pinfunction "DRAM_D57_AA21") (pintype "bidirectional"))
      (node (ref "U4") (pin "G2") (pinfunction "DQ6_G2") (pintype "bidirectional"))
    )
    (net (code "88") (name "/DRAM_D58") (class "Default")
      (node (ref "U1") (pin "Y25") (pinfunction "DRAM_D58_Y25") (pintype "bidirectional"))
      (node (ref "U4") (pin "H7") (pinfunction "DQ7_H7") (pintype "bidirectional"))
    )
    (net (code "89") (name "/DRAM_D59") (class "Default")
      (node (ref "U1") (pin "Y22") (pinfunction "DRAM_D59_Y22") (pintype "bidirectional"))
      (node (ref "U4") (pin "F7") (pinfunction "DQ1_F7") (pintype "bidirectional"))
    )
    (net (code "90") (name "/DRAM_D60") (class "Default")
      (node (ref "U1") (pin "AB23") (pinfunction "DRAM_D60_AB23") (pintype "bidirectional"))
      (node (ref "U4") (pin "H3") (pinfunction "DQ4_H3") (pintype "bidirectional"))
    )
    (net (code "91") (name "/DRAM_D61") (class "Default")
      (node (ref "U1") (pin "AA23") (pinfunction "DRAM_D61_AA23") (pintype "bidirectional"))
      (node (ref "U4") (pin "F2") (pinfunction "DQ2_F2") (pintype "bidirectional"))
    )
    (net (code "92") (name "/DRAM_D62") (class "Default")
      (node (ref "U1") (pin "Y23") (pinfunction "DRAM_D62_Y23") (pintype "bidirectional"))
      (node (ref "U4") (pin "F8") (pinfunction "DQ3_F8") (pintype "bidirectional"))
    )
    (net (code "93") (name "/DRAM_D63") (class "Default")
      (node (ref "U1") (pin "W25") (pinfunction "DRAM_D63_W25") (pintype "bidirectional"))
      (node (ref "U4") (pin "H8") (pinfunction "DQ5_H8") (pintype "bidirectional"))
    )
    (net (code "94") (name "/DRAM_DQM0") (class "Default")
      (node (ref "U1") (pin "AC3") (pinfunction "DRAM_DQM0_AC3") (pintype "output"))
      (node (ref "U2") (pin "D3") (pinfunction "UDM_D3") (pintype "input"))
    )
    (net (code "95") (name "/DRAM_DQM1") (class "Default")
      (node (ref "U1") (pin "AC6") (pinfunction "DRAM_DQM1_AC6") (pintype "output"))
      (node (ref "U2") (pin "E7") (pinfunction "LDM_E7") (pintype "input"))
    )
    (net (code "96") (name "/DRAM_DQM2") (class "Default")
      (node (ref "U1") (pin "AB8") (pinfunction "DRAM_DQM2_AB8") (pintype "output"))
      (node (ref "U3") (pin "E7") (pinfunction "LDM_E7") (pintype "input"))
    )
    (net (code "97") (name "/DRAM_DQM3") (class "Default")
      (node (ref "U1") (pin "AE10") (pinfunction "DRAM_DQM3_AE10") (pintype "output"))
      (node (ref "U3") (pin "D3") (pinfunction "UDM_D3") (pintype "input"))
    )
    (net (code "98") (name "/DRAM_DQM4") (class "Default")
      (node (ref "U1") (pin "AB18") (pinfunction "DRAM_DQM4_AB18") (pintype "output"))
      (node (ref "U5") (pin "E7") (pinfunction "LDM_E7") (pintype "input"))
    )
    (net (code "99") (name "/DRAM_DQM5") (class "Default")
      (node (ref "U1") (pin "AC20") (pinfunction "DRAM_DQM5_AC20") (pintype "output"))
      (node (ref "U5") (pin "D3") (pinfunction "UDM_D3") (pintype "input"))
    )
    (net (code "100") (name "/DRAM_DQM6") (class "Default")
      (node (ref "U1") (pin "AD24") (pinfunction "DRAM_DQM6_AD24") (pintype "output"))
      (node (ref "U4") (pin "D3") (pinfunction "UDM_D3") (pintype "input"))
    )
    (net (code "101") (name "/DRAM_DQM7") (class "Default")
      (node (ref "U1") (pin "Y21") (pinfunction "DRAM_DQM7_Y21") (pintype "output"))
      (node (ref "U4") (pin "E7") (pinfunction "LDM_E7") (pintype "input"))
    )
    (net (code "102") (name "/DRAM_DQS0_N") (class "Default")
      (node (ref "U1") (pin "AD3") (pinfunction "~{DRAM_SDQS0}_AD3") (pintype "bidirectional"))
      (node (ref "U2") (pin "B7") (pinfunction "~{UDQS}_B7") (pintype "bidirectional"))
    )
    (net (code "103") (name "/DRAM_DQS0_P") (class "Default")
      (node (ref "U1") (pin "AE3") (pinfunction "DRAM_SDQS0_AE3") (pintype "bidirectional"))
      (node (ref "U2") (pin "C7") (pinfunction "UDQS_C7") (pintype "bidirectional"))
    )
    (net (code "104") (name "/DRAM_DQS1_N") (class "Default")
      (node (ref "U1") (pin "AE6") (pinfunction "~{DRAM_SDQS1}_AE6") (pintype "bidirectional"))
      (node (ref "U2") (pin "G3") (pinfunction "~{LDQS}_G3") (pintype "bidirectional"))
    )
    (net (code "105") (name "/DRAM_DQS1_P") (class "Default")
      (node (ref "U1") (pin "AD6") (pinfunction "DRAM_SDQS1_AD6") (pintype "bidirectional"))
      (node (ref "U2") (pin "F3") (pinfunction "LDQS_F3") (pintype "bidirectional"))
    )
    (net (code "106") (name "/DRAM_DQS2_N") (class "Default")
      (node (ref "U1") (pin "AE8") (pinfunction "~{DRAM_SDQS2}_AE8") (pintype "bidirectional"))
      (node (ref "U3") (pin "G3") (pinfunction "~{LDQS}_G3") (pintype "bidirectional"))
    )
    (net (code "107") (name "/DRAM_DQS2_P") (class "Default")
      (node (ref "U1") (pin "AD8") (pinfunction "DRAM_SDQS2_AD8") (pintype "bidirectional"))
      (node (ref "U3") (pin "F3") (pinfunction "LDQS_F3") (pintype "bidirectional"))
    )
    (net (code "108") (name "/DRAM_DQS3_N") (class "Default")
      (node (ref "U1") (pin "AB10") (pinfunction "~{DRAM_SDQS3}_AB10") (pintype "bidirectional"))
      (node (ref "U3") (pin "B7") (pinfunction "~{UDQS}_B7") (pintype "bidirectional"))
    )
    (net (code "109") (name "/DRAM_DQS3_P") (class "Default")
      (node (ref "U1") (pin "AC10") (pinfunction "DRAM_SDQS3_AC10") (pintype "bidirectional"))
      (node (ref "U3") (pin "C7") (pinfunction "UDQS_C7") (pintype "bidirectional"))
    )
    (net (code "110") (name "/DRAM_DQS4_N") (class "Default")
      (node (ref "U1") (pin "AE18") (pinfunction "~{DRAM_SDQS4}_AE18") (pintype "bidirectional"))
      (node (ref "U5") (pin "G3") (pinfunction "~{LDQS}_G3") (pintype "bidirectional"))
    )
    (net (code "111") (name "/DRAM_DQS4_P") (class "Default")
      (node (ref "U1") (pin "AD18") (pinfunction "DRAM_SDQS4_AD18") (pintype "bidirectional"))
      (node (ref "U5") (pin "F3") (pinfunction "LDQS_F3") (pintype "bidirectional"))
    )
    (net (code "112") (name "/DRAM_DQS5_N") (class "Default")
      (node (ref "U1") (pin "AE20") (pinfunction "~{DRAM_SDQS5}_AE20") (pintype "bidirectional"))
      (node (ref "U5") (pin "B7") (pinfunction "~{UDQS}_B7") (pintype "bidirectional"))
    )
    (net (code "113") (name "/DRAM_DQS5_P") (class "Default")
      (node (ref "U1") (pin "AD20") (pinfunction "DRAM_SDQS5_AD20") (pintype "bidirectional"))
      (node (ref "U5") (pin "C7") (pinfunction "UDQS_C7") (pintype "bidirectional"))
    )
    (net (code "114") (name "/DRAM_DQS6_N") (class "Default")
      (node (ref "U1") (pin "AE23") (pinfunction "~{DRAM_SDQS6}_AE23") (pintype "bidirectional"))
      (node (ref "U4") (pin "B7") (pinfunction "~{UDQS}_B7") (pintype "bidirectional"))
    )
    (net (code "115") (name "/DRAM_DQS6_P") (class "Default")
      (node (ref "U1") (pin "AD23") (pinfunction "DRAM_SDQS6_AD23") (pintype "bidirectional"))
      (node (ref "U4") (pin "C7") (pinfunction "UDQS_C7") (pintype "bidirectional"))
    )
    (net (code "116") (name "/DRAM_DQS7_N") (class "Default")
      (node (ref "U1") (pin "AA24") (pinfunction "~{DRAM_SDQS7}_AA24") (pintype "bidirectional"))
      (node (ref "U4") (pin "G3") (pinfunction "~{LDQS}_G3") (pintype "bidirectional"))
    )
    (net (code "117") (name "/DRAM_DQS7_P") (class "Default")
      (node (ref "U1") (pin "AA25") (pinfunction "DRAM_SDQS7_AA25") (pintype "bidirectional"))
      (node (ref "U4") (pin "F3") (pinfunction "LDQS_F3") (pintype "bidirectional"))
    )
    (net (code "119") (name "/DRAM_RAS_B") (class "Default")
      (node (ref "U1") (pin "AB15") (pinfunction "DRAM_RAS_AB15") (pintype "output"))
      (node (ref "U2") (pin "J3") (pinfunction "~{RAS}_J3") (pintype "input"))
      (node (ref "U3") (pin "J3") (pinfunction "~{RAS}_J3") (pintype "input"))
      (node (ref "U4") (pin "J3") (pinfunction "~{RAS}_J3") (pintype "input"))
      (node (ref "U5") (pin "J3") (pinfunction "~{RAS}_J3") (pintype "input"))
    )
    (net (code "120") (name "/DRAM_RESET_B") (class "Default")
      (node (ref "R7") (pin "2") (pinfunction "2_2") (pintype "passive"))
      (node (ref "U1") (pin "Y6") (pinfunction "DRAM_RESET_Y6") (pintype "output"))
      (node (ref "U2") (pin "T2") (pinfunction "~{RESET}_T2") (pintype "input"))
      (node (ref "U3") (pin "T2") (pinfunction "~{RESET}_T2") (pintype "input"))
      (node (ref "U4") (pin "T2") (pinfunction "~{RESET}_T2") (pintype "input"))
      (node (ref "U5") (pin "T2") (pinfunction "~{RESET}_T2") (pintype "input"))
    )
    (net (code "121") (name "/DRAM_SDBA0") (class "Default")
      (node (ref "U1") (pin "AC15") (pinfunction "DRAM_SDBA0_AC15") (pintype "output"))
      (node (ref "U2") (pin "M2") (pinfunction "BA0_M2") (pintype "input"))
      (node (ref "U3") (pin "M2") (pinfunction "BA0_M2") (pintype "input"))
      (node (ref "U4") (pin "M2") (pinfunction "BA0_M2") (pintype "input"))
      (node (ref "U5") (pin "M2") (pinfunction "BA0_M2") (pintype "input"))
    )
    (net (code "122") (name "/DRAM_SDBA1") (class "Default")
      (node (ref "U1") (pin "Y15") (pinfunction "DRAM_SDBA1_Y15") (pintype "output"))
      (node (ref "U2") (pin "N8") (pinfunction "BA1_N8") (pintype "input"))
      (node (ref "U3") (pin "N8") (pinfunction "BA1_N8") (pintype "input"))
      (node (ref "U4") (pin "N8") (pinfunction "BA1_N8") (pintype "input"))
      (node (ref "U5") (pin "N8") (pinfunction "BA1_N8") (pintype "input"))
    )
    (net (code "123") (name "/DRAM_SDBA2") (class "Default")
      (node (ref "U1") (pin "AB12") (pinfunction "DRAM_SDBA2_AB12") (pintype "output"))
      (node (ref "U2") (pin "M3") (pinfunction "BA2_M3") (pintype "input"))
      (node (ref "U3") (pin "M3") (pinfunction "BA2_M3") (pintype "input"))
      (node (ref "U4") (pin "M3") (pinfunction "BA2_M3") (pintype "input"))
      (node (ref "U5") (pin "M3") (pinfunction "BA2_M3") (pintype "input"))
    )
    (net (code "124") (name "/DRAM_SDCKE0") (class "Default")
      (node (ref "R6") (pin "2") (pinfunction "2_2") (pintype "passive"))
      (node (ref "U1") (pin "Y11") (pinfunction "DRAM_SDCKE0_Y11") (pintype "output"))
      (node (ref "U2") (pin "K9") (pinfunction "CKE_K9") (pintype "input"))
      (node (ref "U3") (pin "K9") (pinfunction "CKE_K9") (pintype "input"))
      (node (ref "U4") (pin "K9") (pinfunction "CKE_K9") (pintype "input"))
      (node (ref "U5") (pin "K9") (pinfunction "CKE_K9") (pintype "input"))
    )
    (net (code "125") (name "/DRAM_SDODT0") (class "Default")
      (node (ref "U1") (pin "AC16") (pinfunction "DRAM_SDODT0_AC16") (pintype "output"))
      (node (ref "U2") (pin "K1") (pinfunction "ODT_K1") (pintype "input"))
      (node (ref "U3") (pin "K1") (pinfunction "ODT_K1") (pintype "input"))
      (node (ref "U4") (pin "K1") (pinfunction "ODT_K1") (pintype "input"))
      (node (ref "U5") (pin "K1") (pinfunction "ODT_K1") (pintype "input"))
    )
    (net (code "126") (name "/DRAM_WE_B") (class "Default")
      (node (ref "U1") (pin "AB16") (pinfunction "DRAM_SDWE_AB16") (pintype "output"))
      (node (ref "U2") (pin "L3") (pinfunction "~{WE}_L3") (pintype "input"))
      (node (ref "U3") (pin "L3") (pinfunction "~{WE}_L3") (pintype "input"))
      (node (ref "U4") (pin "L3") (pinfunction "~{WE}_L3") (pintype "input"))
      (node (ref "U5") (pin "L3") (pinfunction "~{WE}_L3") (pintype "input"))
    )
    (net (code "127") (name "/ZQPAD") (class "Default")
      (node (ref "R10") (pin "1") (pinfunction "1_1") (pintype "passive"))
      (node (ref "U1") (pin "AE17") (pinfunction "ZQPAD_AE17") (pintype "passive"))
    )
    (net (code "128") (name "GND") (class "Default")
      (node (ref "C10") (pin "2") (pinfunction "2_2") (pintype "passive"))
      (node (ref "C11") (pin "2") (pinfunction "2_2") (pintype "passive"))
      (node (ref "C12") (pin "2") (pinfunction "2_2") (pintype "passive"))
      (node (ref "C13") (pin "2") (pinfunction "2_2") (pintype "passive"))
      (node (ref "C14") (pin "2") (pinfunction "2_2") (pintype "passive"))
      (node (ref "C15") (pin "2") (pinfunction "2_2") (pintype "passive"))
      (node (ref "C16") (pin "2") (pinfunction "2_2") (pintype "passive"))
      (node (ref "C17") (pin "2") (pinfunction "2_2") (pintype "passive"))
      (node (ref "C19") (pin "2") (pinfunction "2_2") (pintype "passive"))
      (node (ref "C20") (pin "2") (pinfunction "2_2") (pintype "passive"))
      (node (ref "C21") (pin "2") (pinfunction "2_2") (pintype "passive"))
      (node (ref "C22") (pin "2") (pinfunction "2_2") (pintype "passive"))
      (node (ref "C23") (pin "2") (pinfunction "2_2") (pintype "passive"))
      (node (ref "C24") (pin "2") (pinfunction "2_2") (pintype "passive"))
      (node (ref "C25") (pin "2") (pinfunction "2_2") (pintype "passive"))
      (node (ref "C26") (pin "2") (pinfunction "2_2") (pintype "passive"))
      (node (ref "C27") (pin "2") (pinfunction "2_2") (pintype "passive"))
      (node (ref "C28") (pin "2") (pinfunction "2_2") (pintype "passive"))
      (node (ref "C29") (pin "2") (pinfunction "2_2") (pintype "passive"))
      (node (ref "C3") (pin "2") (pinfunction "2_2") (pintype "passive"))
      (node (ref "C30") (pin "2") (pinfunction "2_2") (pintype "passive"))
      (node (ref "C31") (pin "2") (pinfunction "2_2") (pintype "passive"))
      (node (ref "C32") (pin "2") (pinfunction "2_2") (pintype "passive"))
      (node (ref "C33") (pin "2") (pinfunction "2_2") (pintype "passive"))
      (node (ref "C34") (pin "2") (pinfunction "2_2") (pintype "passive"))
      (node (ref "C35") (pin "2") (pinfunction "2_2") (pintype "passive"))
      (node (ref "C36") (pin "2") (pinfunction "2_2") (pintype "passive"))
      (node (ref "C37") (pin "2") (pinfunction "2_2") (pintype "passive"))
      (node (ref "C38") (pin "2") (pinfunction "2_2") (pintype "passive"))
      (node (ref "C39") (pin "2") (pinfunction "2_2") (pintype "passive"))
      (node (ref "C4") (pin "2") (pinfunction "2_2") (pintype "passive"))
      (node (ref "C40") (pin "2") (pinfunction "2_2") (pintype "passive"))
      (node (ref "C41") (pin "2") (pinfunction "2_2") (pintype "passive"))
      (node (ref "C42") (pin "2") (pinfunction "2_2") (pintype "passive"))
      (node (ref "C43") (pin "2") (pinfunction "2_2") (pintype "passive"))
      (node (ref "C44") (pin "2") (pinfunction "2_2") (pintype "passive"))
      (node (ref "C45") (pin "2") (pinfunction "2_2") (pintype "passive"))
      (node (ref "C46") (pin "2") (pinfunction "2_2") (pintype "passive"))
      (node (ref "C47") (pin "2") (pinfunction "2_2") (pintype "passive"))
      (node (ref "C48") (pin "2") (pinfunction "2_2") (pintype "passive"))
      (node (ref "C49") (pin "2") (pinfunction "2_2") (pintype "passive"))
      (node (ref "C5") (pin "2") (pinfunction "2_2") (pintype "passive"))
      (node (ref "C50") (pin "2") (pinfunction "2_2") (pintype "passive"))
      (node (ref "C51") (pin "2") (pinfunction "2_2") (pintype "passive"))
      (node (ref "C52") (pin "2") (pinfunction "2_2") (pintype "passive"))
      (node (ref "C53") (pin "2") (pinfunction "2_2") (pintype "passive"))
      (node (ref "C54") (pin "2") (pinfunction "2_2") (pintype "passive"))
      (node (ref "C55") (pin "2") (pinfunction "2_2") (pintype "passive"))
      (node (ref "C56") (pin "2") (pinfunction "2_2") (pintype "passive"))
      (node (ref "C57") (pin "2") (pinfunction "2_2") (pintype "passive"))
      (node (ref "C58") (pin "2") (pinfunction "2_2") (pintype "passive"))
      (node (ref "C59") (pin "2") (pinfunction "2_2") (pintype "passive"))
      (node (ref "C6") (pin "2") (pinfunction "2_2") (pintype "passive"))
      (node (ref "C60") (pin "2") (pinfunction "2_2") (pintype "passive"))
      (node (ref "C7") (pin "2") (pinfunction "2_2") (pintype "passive"))
      (node (ref "C8") (pin "2") (pinfunction "2_2") (pintype "passive"))
      (node (ref "C9") (pin "2") (pinfunction "2_2") (pintype "passive"))
      (node (ref "R10") (pin "2") (pinfunction "2_2") (pintype "passive"))
      (node (ref "R12") (pin "1") (pinfunction "1_1") (pintype "passive"))
      (node (ref "R4") (pin "1") (pinfunction "1_1") (pintype "passive"))
      (node (ref "R5") (pin "1") (pinfunction "1_1") (pintype "passive"))
      (node (ref "R6") (pin "1") (pinfunction "1_1") (pintype "passive"))
      (node (ref "R7") (pin "1") (pinfunction "1_1") (pintype "passive"))
      (node (ref "R8") (pin "1") (pinfunction "1_1") (pintype "passive"))
      (node (ref "R9") (pin "1") (pinfunction "1_1") (pintype "passive"))
      (node (ref "U2") (pin "A9") (pinfunction "VSS1_A9") (pintype "power_in"))
      (node (ref "U2") (pin "B1") (pinfunction "VSSQ1_B1") (pintype "power_in"))
      (node (ref "U2") (pin "B3") (pinfunction "VSS2_B3") (pintype "power_in"))
      (node (ref "U2") (pin "B9") (pinfunction "VSSQ2_B9") (pintype "power_in"))
      (node (ref "U2") (pin "D1") (pinfunction "VSSQ3_D1") (pintype "power_in"))
      (node (ref "U2") (pin "D8") (pinfunction "VSSQ4_D8") (pintype "power_in"))
      (node (ref "U2") (pin "E1") (pinfunction "VSS3_E1") (pintype "power_in"))
      (node (ref "U2") (pin "E2") (pinfunction "VSSQ5_E2") (pintype "power_in"))
      (node (ref "U2") (pin "E8") (pinfunction "VSSQ6_E8") (pintype "power_in"))
      (node (ref "U2") (pin "F9") (pinfunction "VSSQ7_F9") (pintype "power_in"))
      (node (ref "U2") (pin "G1") (pinfunction "VSSQ8_G1") (pintype "power_in"))
      (node (ref "U2") (pin "G8") (pinfunction "VSS4_G8") (pintype "power_in"))
      (node (ref "U2") (pin "G9") (pinfunction "VSSQ9_G9") (pintype "power_in"))
      (node (ref "U2") (pin "J2") (pinfunction "VSS5_J2") (pintype "power_in"))
      (node (ref "U2") (pin "J8") (pinfunction "VSS6_J8") (pintype "power_in"))
      (node (ref "U2") (pin "M1") (pinfunction "VSS7_M1") (pintype "power_in"))
      (node (ref "U2") (pin "M9") (pinfunction "VSS8_M9") (pintype "power_in"))
      (node (ref "U2") (pin "P1") (pinfunction "VSS9_P1") (pintype "power_in"))
      (node (ref "U2") (pin "P9") (pinfunction "VSS10_P9") (pintype "power_in"))
      (node (ref "U2") (pin "T1") (pinfunction "VSS11_T1") (pintype "power_in"))
      (node (ref "U2") (pin "T9") (pinfunction "VSS12_T9") (pintype "power_in"))
      (node (ref "U3") (pin "A9") (pinfunction "VSS1_A9") (pintype "power_in"))
      (node (ref "U3") (pin "B1") (pinfunction "VSSQ1_B1") (pintype "power_in"))
      (node (ref "U3") (pin "B3") (pinfunction "VSS2_B3") (pintype "power_in"))
      (node (ref "U3") (pin "B9") (pinfunction "VSSQ2_B9") (pintype "power_in"))
      (node (ref "U3") (pin "D1") (pinfunction "VSSQ3_D1") (pintype "power_in"))
      (node (ref "U3") (pin "D8") (pinfunction "VSSQ4_D8") (pintype "power_in"))
      (node (ref "U3") (pin "E1") (pinfunction "VSS3_E1") (pintype "power_in"))
      (node (ref "U3") (pin "E2") (pinfunction "VSSQ5_E2") (pintype "power_in"))
      (node (ref "U3") (pin "E8") (pinfunction "VSSQ6_E8") (pintype "power_in"))
      (node (ref "U3") (pin "F9") (pinfunction "VSSQ7_F9") (pintype "power_in"))
      (node (ref "U3") (pin "G1") (pinfunction "VSSQ8_G1") (pintype "power_in"))
      (node (ref "U3") (pin "G8") (pinfunction "VSS4_G8") (pintype "power_in"))
      (node (ref "U3") (pin "G9") (pinfunction "VSSQ9_G9") (pintype "power_in"))
      (node (ref "U3") (pin "J2") (pinfunction "VSS5_J2") (pintype "power_in"))
      (node (ref "U3") (pin "J8") (pinfunction "VSS6_J8") (pintype "power_in"))
      (node (ref "U3") (pin "M1") (pinfunction "VSS7_M1") (pintype "power_in"))
      (node (ref "U3") (pin "M9") (pinfunction "VSS8_M9") (pintype "power_in"))
      (node (ref "U3") (pin "P1") (pinfunction "VSS9_P1") (pintype "power_in"))
      (node (ref "U3") (pin "P9") (pinfunction "VSS10_P9") (pintype "power_in"))
      (node (ref "U3") (pin "T1") (pinfunction "VSS11_T1") (pintype "power_in"))
      (node (ref "U3") (pin "T9") (pinfunction "VSS12_T9") (pintype "power_in"))
      (node (ref "U4") (pin "A9") (pinfunction "VSS1_A9") (pintype "power_in"))
      (node (ref "U4") (pin "B1") (pinfunction "VSSQ1_B1") (pintype "power_in"))
      (node (ref "U4") (pin "B3") (pinfunction "VSS2_B3") (pintype "power_in"))
      (node (ref "U4") (pin "B9") (pinfunction "VSSQ2_B9") (pintype "power_in"))
      (node (ref "U4") (pin "D1") (pinfunction "VSSQ3_D1") (pintype "power_in"))
      (node (ref "U4") (pin "D8") (pinfunction "VSSQ4_D8") (pintype "power_in"))
      (node (ref "U4") (pin "E1") (pinfunction "VSS3_E1") (pintype "power_in"))
      (node (ref "U4") (pin "E2") (pinfunction "VSSQ5_E2") (pintype "power_in"))
      (node (ref "U4") (pin "E8") (pinfunction "VSSQ6_E8") (pintype "power_in"))
      (node (ref "U4") (pin "F9") (pinfunction "VSSQ7_F9") (pintype "power_in"))
      (node (ref "U4") (pin "G1") (pinfunction "VSSQ8_G1") (pintype "power_in"))
      (node (ref "U4") (pin "G8") (pinfunction "VSS4_G8") (pintype "power_in"))
      (node (ref "U4") (pin "G9") (pinfunction "VSSQ9_G9") (pintype "power_in"))
      (node (ref "U4") (pin "J2") (pinfunction "VSS5_J2") (pintype "power_in"))
      (node (ref "U4") (pin "J8") (pinfunction "VSS6_J8") (pintype "power_in"))
      (node (ref "U4") (pin "M1") (pinfunction "VSS7_M1") (pintype "power_in"))
      (node (ref "U4") (pin "M9") (pinfunction "VSS8_M9") (pintype "power_in"))
      (node (ref "U4") (pin "P1") (pinfunction "VSS9_P1") (pintype "power_in"))
      (node (ref "U4") (pin "P9") (pinfunction "VSS10_P9") (pintype "power_in"))
      (node (ref "U4") (pin "T1") (pinfunction "VSS11_T1") (pintype "power_in"))
      (node (ref "U4") (pin "T9") (pinfunction "VSS12_T9") (pintype "power_in"))
      (node (ref "U5") (pin "A9") (pinfunction "VSS1_A9") (pintype "power_in"))
      (node (ref "U5") (pin "B1") (pinfunction "VSSQ1_B1") (pintype "power_in"))
      (node (ref "U5") (pin "B3") (pinfunction "VSS2_B3") (pintype "power_in"))
      (node (ref "U5") (pin "B9") (pinfunction "VSSQ2_B9") (pintype "power_in"))
      (node (ref "U5") (pin "D1") (pinfunction "VSSQ3_D1") (pintype "power_in"))
      (node (ref "U5") (pin "D8") (pinfunction "VSSQ4_D8") (pintype "power_in"))
      (node (ref "U5") (pin "E1") (pinfunction "VSS3_E1") (pintype "power_in"))
      (node (ref "U5") (pin "E2") (pinfunction "VSSQ5_E2") (pintype "power_in"))
      (node (ref "U5") (pin "E8") (pinfunction "VSSQ6_E8") (pintype "power_in"))
      (node (ref "U5") (pin "F9") (pinfunction "VSSQ7_F9") (pintype "power_in"))
      (node (ref "U5") (pin "G1") (pinfunction "VSSQ8_G1") (pintype "power_in"))
      (node (ref "U5") (pin "G8") (pinfunction "VSS4_G8") (pintype "power_in"))
      (node (ref "U5") (pin "G9") (pinfunction "VSSQ9_G9") (pintype "power_in"))
      (node (ref "U5") (pin "J2") (pinfunction "VSS5_J2") (pintype "power_in"))
      (node (ref "U5") (pin "J8") (pinfunction "VSS6_J8") (pintype "power_in"))
      (node (ref "U5") (pin "M1") (pinfunction "VSS7_M1") (pintype "power_in"))
      (node (ref "U5") (pin "M9") (pinfunction "VSS8_M9") (pintype "power_in"))
      (node (ref "U5") (pin "P1") (pinfunction "VSS9_P1") (pintype "power_in"))
      (node (ref "U5") (pin "P9") (pinfunction "VSS10_P9") (pintype "power_in"))
      (node (ref "U5") (pin "T1") (pinfunction "VSS11_T1") (pintype "power_in"))
      (node (ref "U5") (pin "T9") (pinfunction "VSS12_T9") (pintype "power_in"))
    )
    (net (code "129") (name "unconnected-(U1C-DRAM_CS1-PadAD17)") (class "Default")
      (node (ref "U1") (pin "AD17") (pinfunction "DRAM_CS1_AD17") (pintype "output"))
    )
    (net (code "130") (name "unconnected-(U1C-DRAM_SDCKE1-PadAA11)") (class "Default")
      (node (ref "U1") (pin "AA11") (pinfunction "DRAM_SDCKE1_AA11") (pintype "output"))
    )
    (net (code "131") (name "unconnected-(U1C-DRAM_SDODT1-PadAB17)") (class "Default")
      (node (ref "U1") (pin "AB17") (pinfunction "DRAM_SDODT1_AB17") (pintype "output"))
    )
    (net (code "132") (name "unconnected-(U2-NC_J1-PadJ1)") (class "Default")
      (node (ref "U2") (pin "J1") (pinfunction "NC_J1_J1") (pintype "passive"))
    )
    (net (code "133") (name "unconnected-(U2-NC_J9-PadJ9)") (class "Default")
      (node (ref "U2") (pin "J9") (pinfunction "NC_J9_J9") (pintype "passive"))
    )
    (net (code "134") (name "unconnected-(U2-NC_L1-PadL1)") (class "Default")
      (node (ref "U2") (pin "L1") (pinfunction "NC_L1_L1") (pintype "passive"))
    )
    (net (code "135") (name "unconnected-(U2-NC_L9-PadL9)") (class "Default")
      (node (ref "U2") (pin "L9") (pinfunction "NC_L9_L9") (pintype "passive"))
    )
    (net (code "136") (name "unconnected-(U3-NC_J1-PadJ1)") (class "Default")
      (node (ref "U3") (pin "J1") (pinfunction "NC_J1_J1") (pintype "passive"))
    )
    (net (code "137") (name "unconnected-(U3-NC_J9-PadJ9)") (class "Default")
      (node (ref "U3") (pin "J9") (pinfunction "NC_J9_J9") (pintype "passive"))
    )
    (net (code "138") (name "unconnected-(U3-NC_L1-PadL1)") (class "Default")
      (node (ref "U3") (pin "L1") (pinfunction "NC_L1_L1") (pintype "passive"))
    )
    (net (code "139") (name "unconnected-(U3-NC_L9-PadL9)") (class "Default")
      (node (ref "U3") (pin "L9") (pinfunction "NC_L9_L9") (pintype "passive"))
    )
    (net (code "140") (name "unconnected-(U4-NC_J1-PadJ1)") (class "Default")
      (node (ref "U4") (pin "J1") (pinfunction "NC_J1_J1") (pintype "passive"))
    )
    (net (code "141") (name "unconnected-(U4-NC_J9-PadJ9)") (class "Default")
      (node (ref "U4") (pin "J9") (pinfunction "NC_J9_J9") (pintype "passive"))
    )
    (net (code "142") (name "unconnected-(U4-NC_L1-PadL1)") (class "Default")
      (node (ref "U4") (pin "L1") (pinfunction "NC_L1_L1") (pintype "passive"))
    )
    (net (code "143") (name "unconnected-(U4-NC_L9-PadL9)") (class "Default")
      (node (ref "U4") (pin "L9") (pinfunction "NC_L9_L9") (pintype "passive"))
    )
    (net (code "144") (name "unconnected-(U5-NC_J1-PadJ1)") (class "Default")
      (node (ref "U5") (pin "J1") (pinfunction "NC_J1_J1") (pintype "passive"))
    )
    (net (code "145") (name "unconnected-(U5-NC_J9-PadJ9)") (class "Default")
      (node (ref "U5") (pin "J9") (pinfunction "NC_J9_J9") (pintype "passive"))
    )
    (net (code "146") (name "unconnected-(U5-NC_L1-PadL1)") (class "Default")
      (node (ref "U5") (pin "L1") (pinfunction "NC_L1_L1") (pintype "passive"))
    )
    (net (code "147") (name "unconnected-(U5-NC_L9-PadL9)") (class "Default")
      (node (ref "U5") (pin "L9") (pinfunction "NC_L9_L9") (pintype "passive"))
    )
  )
)
